# boardv3.net
KiCad netlist of a schematic drawn in EAGLE
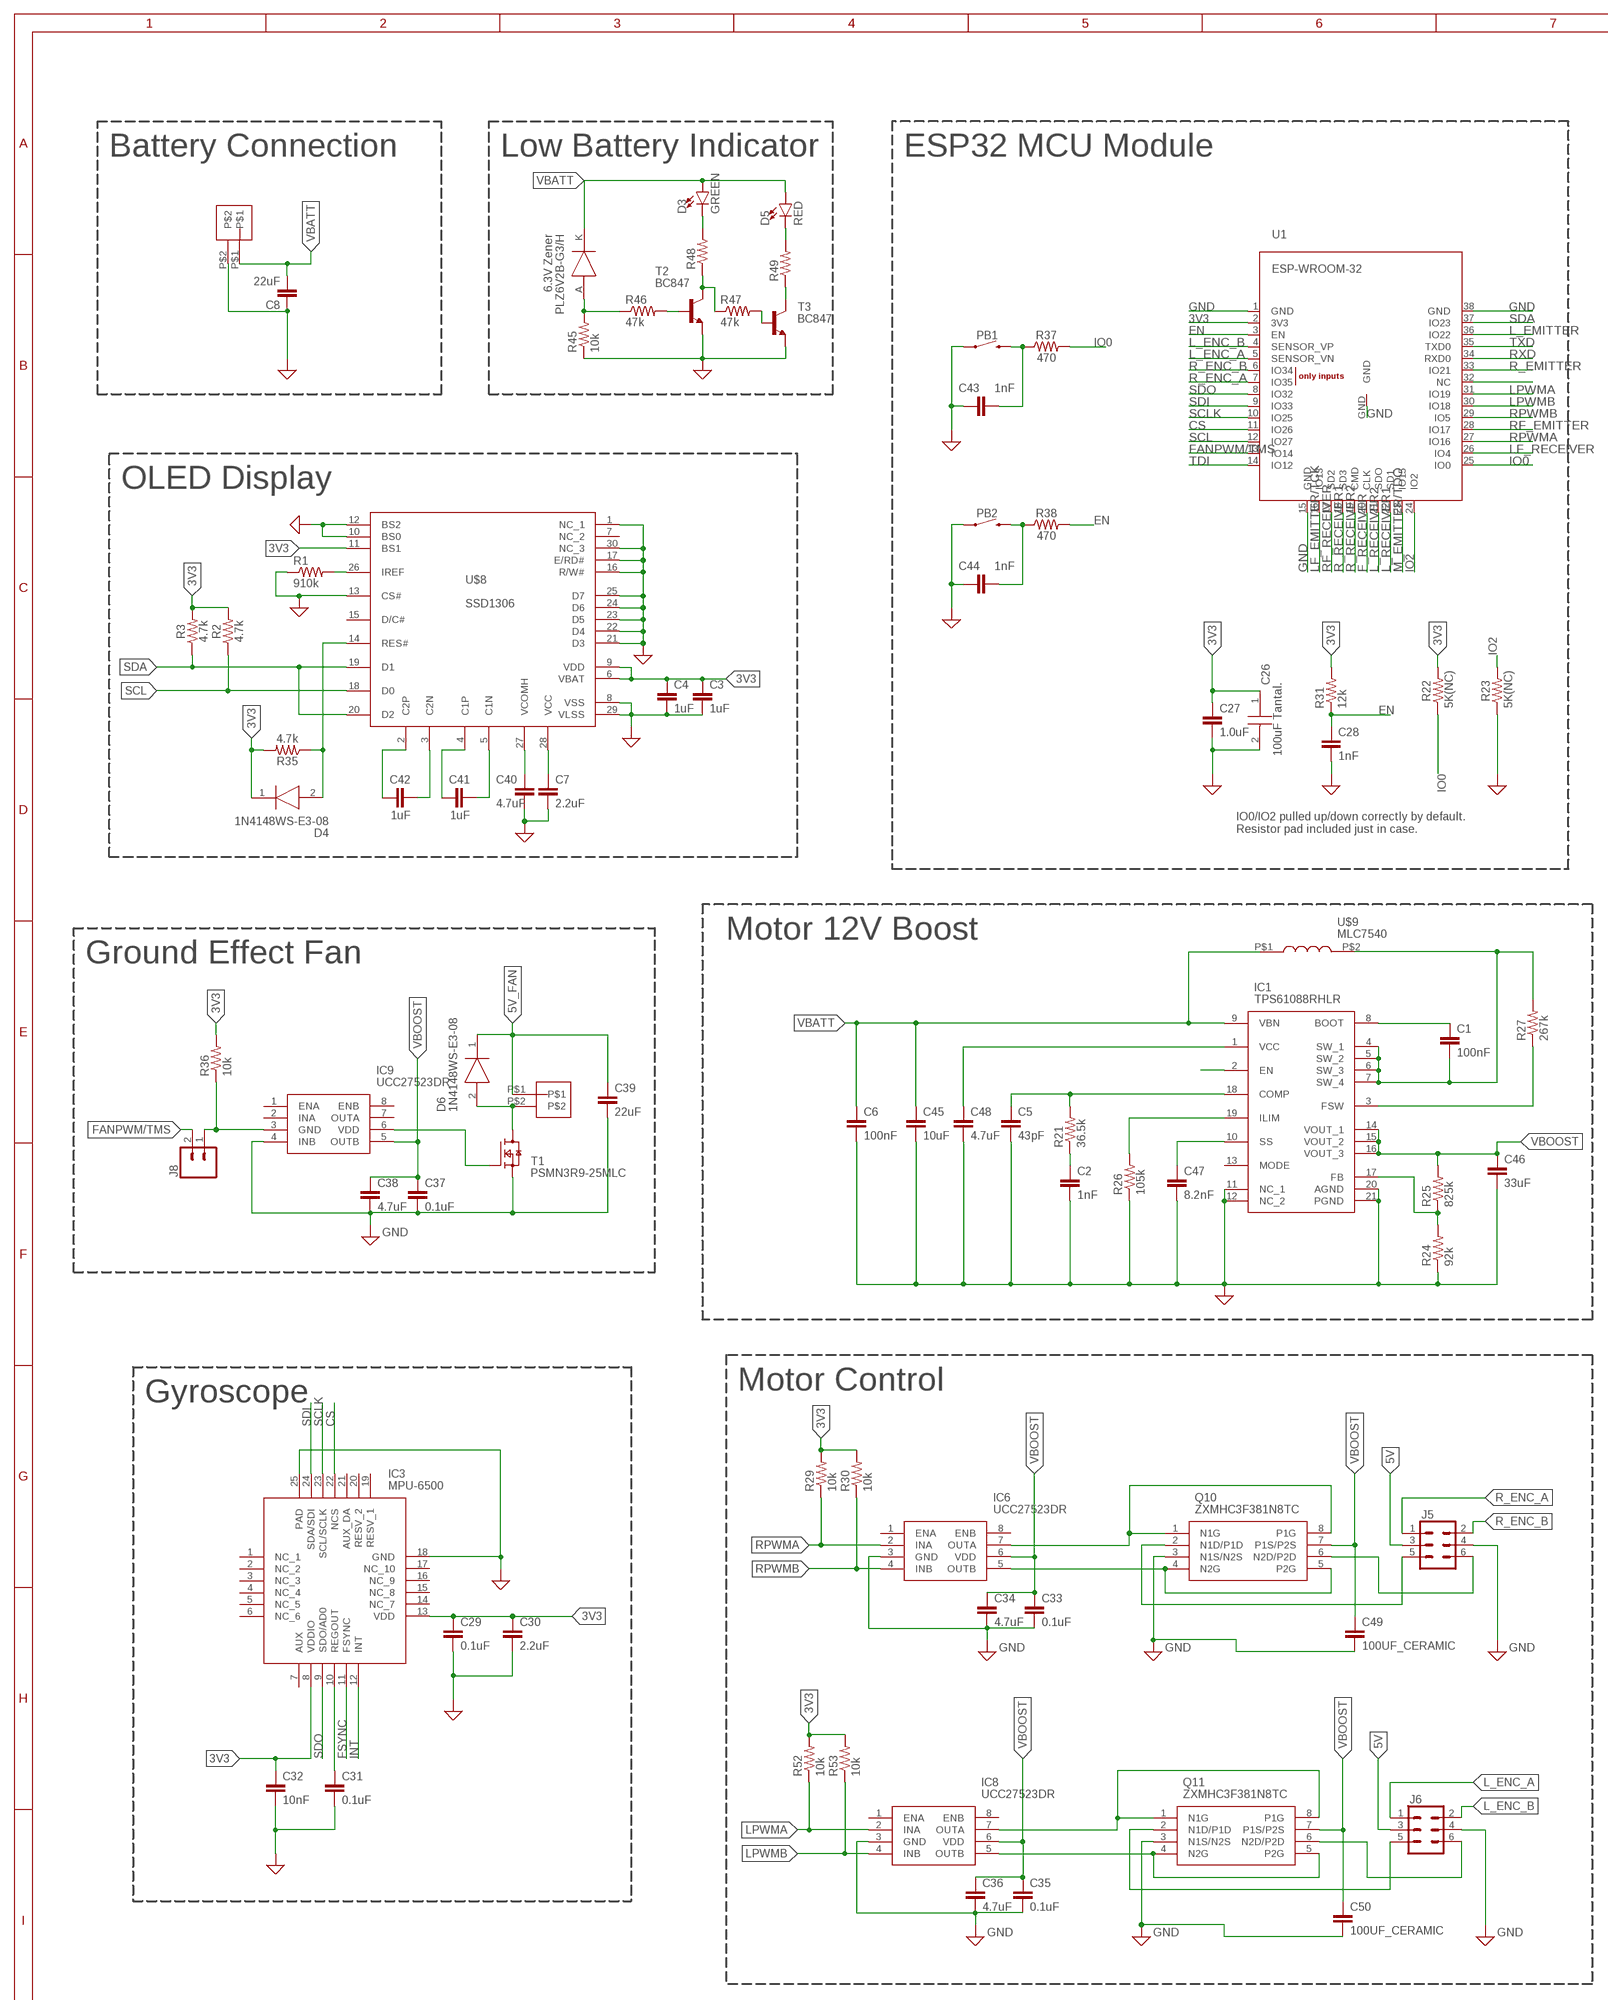
[diagram p0: schematic, sheet 1, part 1 of 2]
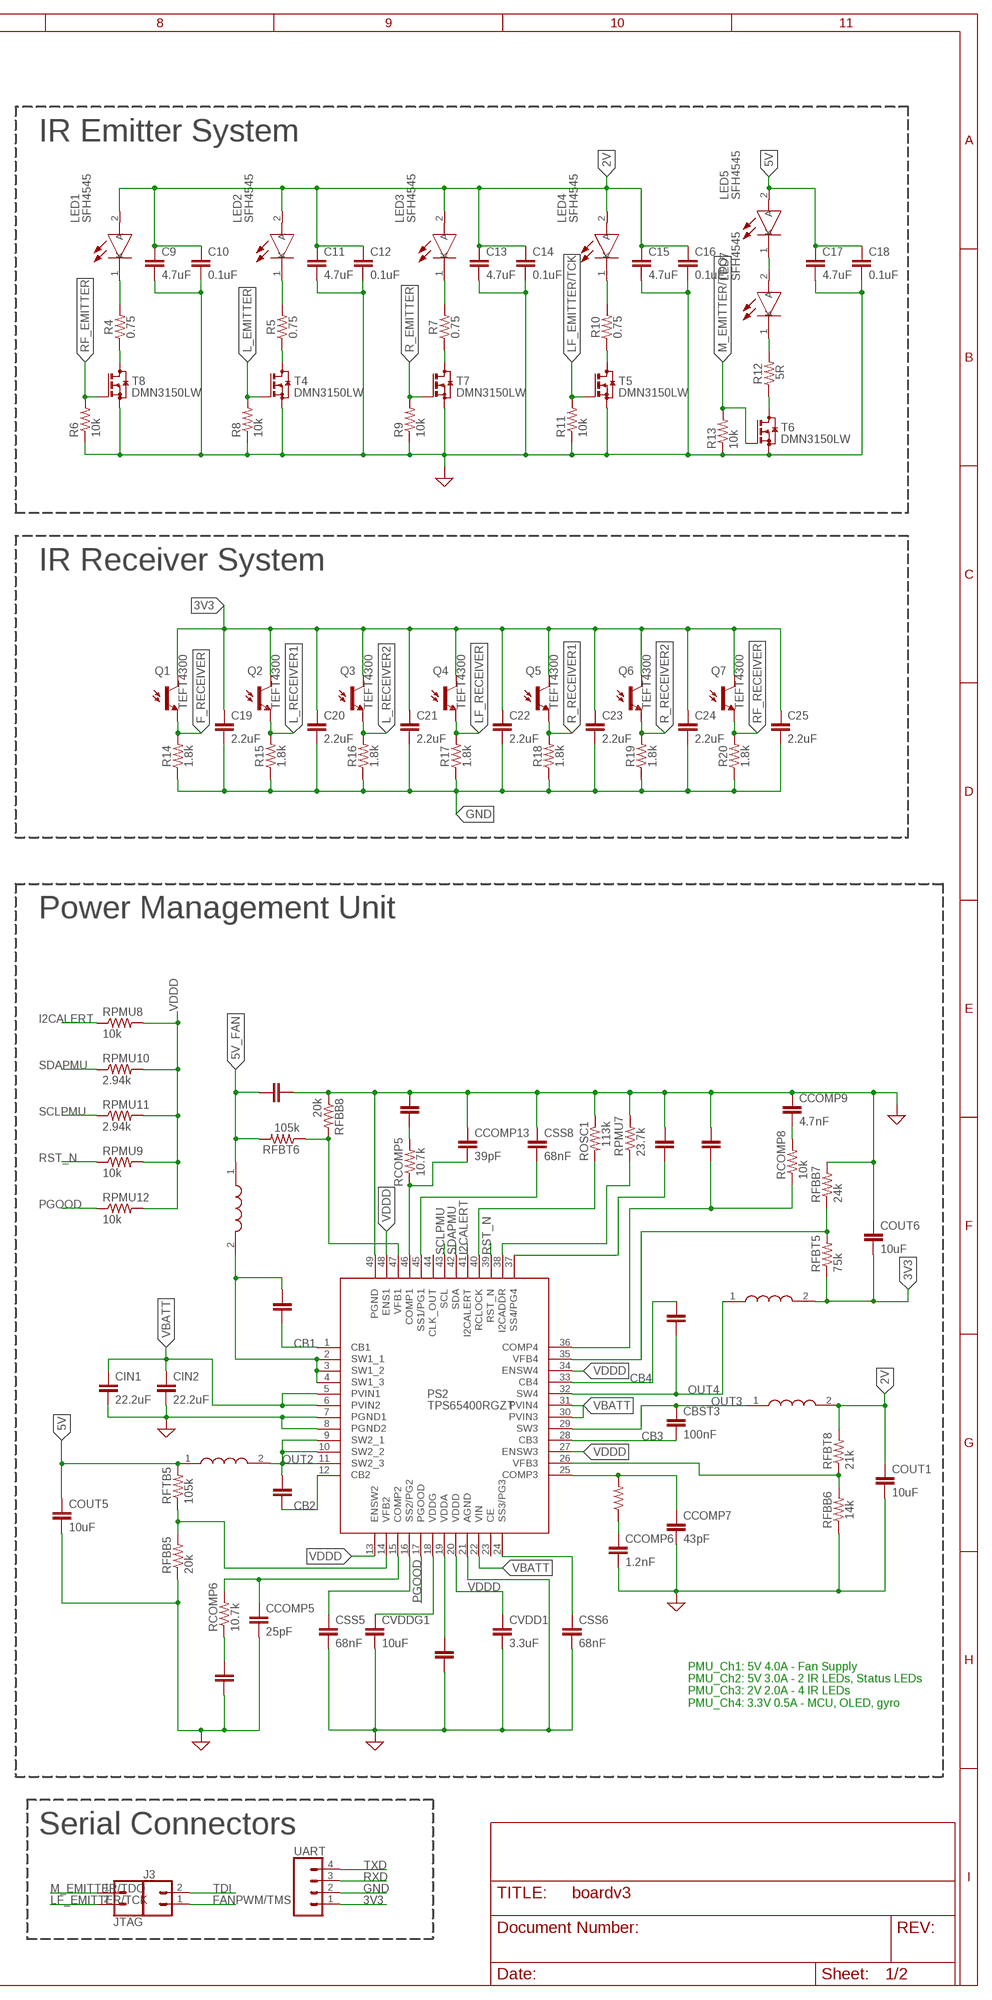
[diagram p1: schematic, sheet 1, part 2 of 2]
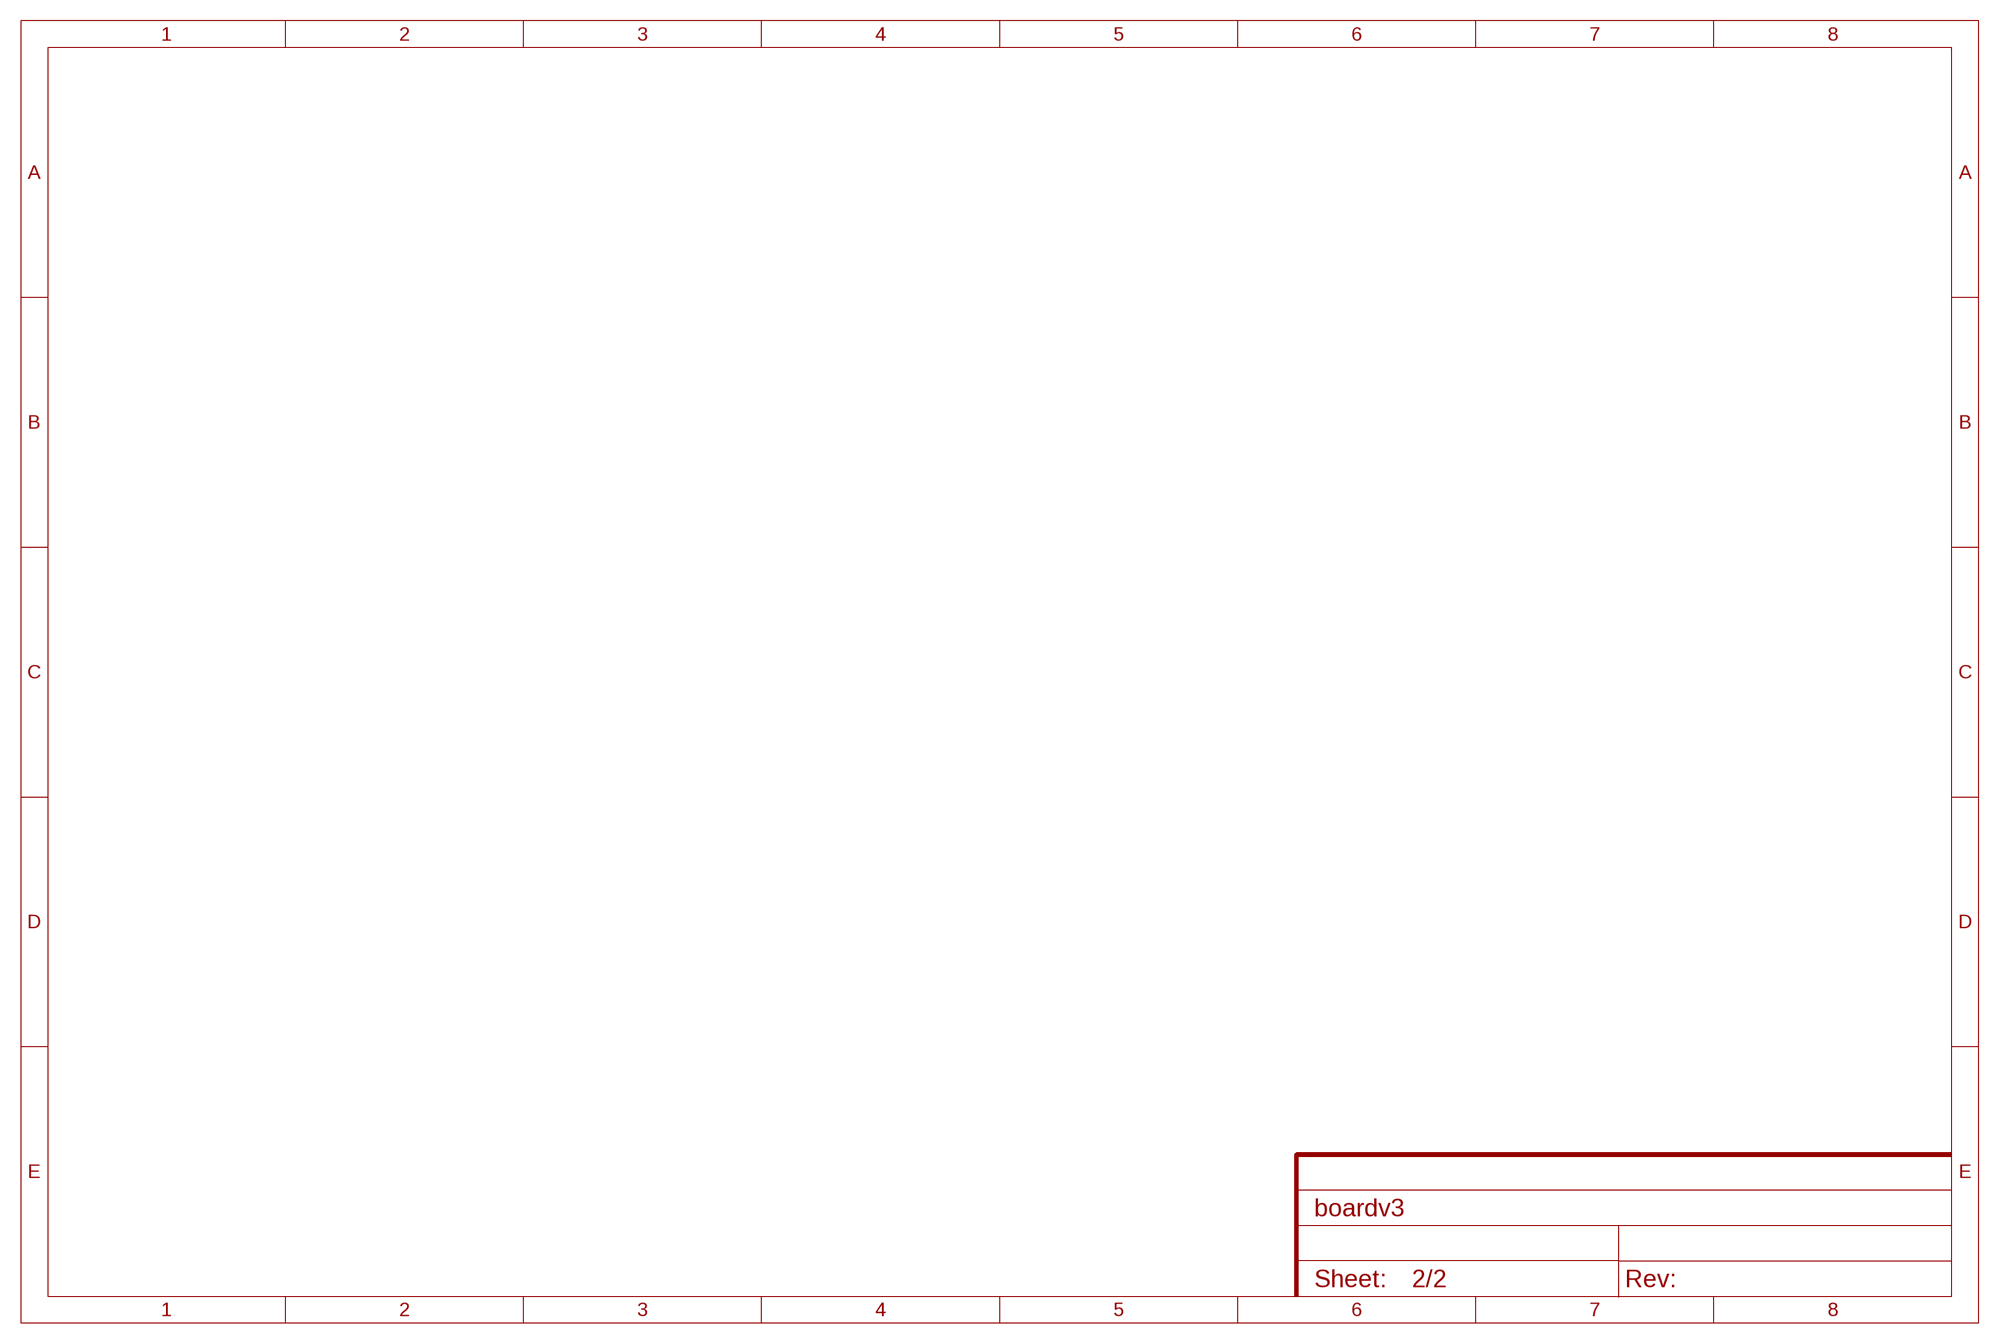
[diagram p2: schematic, sheet 2]

(export (version "E")
  (design (tool "Eeschema 10.0.6"))
  (components
    (comp (ref "C1")
      (value "100nF")
      (footprint "eagle-import:C0402")
      (libsource (lib "eagle-import") (part "C-EUC0402"))
    )
    (comp (ref "C2")
      (value "1nF")
      (footprint "eagle-import:C0805")
      (libsource (lib "eagle-import") (part "C-EUC0805"))
    )
    (comp (ref "C3")
      (value "1uF")
      (footprint "eagle-import:C0402")
      (libsource (lib "eagle-import") (part "resistor_348_C-EUC0402"))
    )
    (comp (ref "C4")
      (value "1uF")
      (footprint "eagle-import:C0402")
      (libsource (lib "eagle-import") (part "resistor_348_C-EUC0402"))
    )
    (comp (ref "C5")
      (value "43pF")
      (footprint "eagle-import:C0402")
      (libsource (lib "eagle-import") (part "C-EUC0402"))
    )
    (comp (ref "C6")
      (value "100nF")
      (footprint "eagle-import:C0805")
      (libsource (lib "eagle-import") (part "C-EUC0805"))
    )
    (comp (ref "C7")
      (value "2.2uF")
      (footprint "eagle-import:C0402")
      (libsource (lib "eagle-import") (part "resistor_348_C-EUC0402"))
    )
    (comp (ref "C8")
      (value "22uF")
      (footprint "eagle-import:0805")
      (libsource (lib "eagle-import") (part "22UF-0805-6.3V-20%"))
    )
    (comp (ref "C9")
      (value "4.7uF")
      (footprint "eagle-import:0603")
      (libsource (lib "eagle-import") (part "4.7UF0603"))
    )
    (comp (ref "C10")
      (value "0.1uF")
      (footprint "eagle-import:C0402")
      (libsource (lib "eagle-import") (part "C-EUC0402"))
    )
    (comp (ref "C11")
      (value "4.7uF")
      (footprint "eagle-import:0603")
      (libsource (lib "eagle-import") (part "4.7UF0603"))
    )
    (comp (ref "C12")
      (value "0.1uF")
      (footprint "eagle-import:C0402")
      (libsource (lib "eagle-import") (part "C-EUC0402"))
    )
    (comp (ref "C13")
      (value "4.7uF")
      (footprint "eagle-import:0603")
      (libsource (lib "eagle-import") (part "4.7UF0603"))
    )
    (comp (ref "C14")
      (value "0.1uF")
      (footprint "eagle-import:C0402")
      (libsource (lib "eagle-import") (part "C-EUC0402"))
    )
    (comp (ref "C15")
      (value "4.7uF")
      (footprint "eagle-import:0603")
      (libsource (lib "eagle-import") (part "4.7UF0603"))
    )
    (comp (ref "C16")
      (value "0.1uF")
      (footprint "eagle-import:C0402")
      (libsource (lib "eagle-import") (part "C-EUC0402"))
    )
    (comp (ref "C17")
      (value "4.7uF")
      (footprint "eagle-import:0603")
      (libsource (lib "eagle-import") (part "4.7UF0603"))
    )
    (comp (ref "C18")
      (value "0.1uF")
      (footprint "eagle-import:C0402")
      (libsource (lib "eagle-import") (part "C-EUC0402"))
    )
    (comp (ref "C19")
      (value "2.2uF")
      (footprint "eagle-import:0603")
      (libsource (lib "eagle-import") (part "2.2UF-0603-10V-20%"))
    )
    (comp (ref "C20")
      (value "2.2uF")
      (footprint "eagle-import:0603")
      (libsource (lib "eagle-import") (part "2.2UF-0603-10V-20%"))
    )
    (comp (ref "C21")
      (value "2.2uF")
      (footprint "eagle-import:0603")
      (libsource (lib "eagle-import") (part "2.2UF-0603-10V-20%"))
    )
    (comp (ref "C22")
      (value "2.2uF")
      (footprint "eagle-import:0603")
      (libsource (lib "eagle-import") (part "2.2UF-0603-10V-20%"))
    )
    (comp (ref "C23")
      (value "2.2uF")
      (footprint "eagle-import:0603")
      (libsource (lib "eagle-import") (part "2.2UF-0603-10V-20%"))
    )
    (comp (ref "C24")
      (value "2.2uF")
      (footprint "eagle-import:0603")
      (libsource (lib "eagle-import") (part "2.2UF-0603-10V-20%"))
    )
    (comp (ref "C25")
      (value "2.2uF")
      (footprint "eagle-import:0603")
      (libsource (lib "eagle-import") (part "2.2UF-0603-10V-20%"))
    )
    (comp (ref "C26")
      (value "100uF Tantal.")
      (footprint "eagle-import:CAPPM3528X210N")
      (fields (field (name "ARROW_PART_NUMBER") "TPSB107K006R0400") (field (name "RS_PART_NUMBER") "1243324"))
      (libsource (lib "eagle-import") (part "TPSB107K006R0400"))
    )
    (comp (ref "C27")
      (value "1.0uF")
      (footprint "eagle-import:0402")
      (libsource (lib "eagle-import") (part "1.0UF-0402-16V-10%"))
    )
    (comp (ref "C28")
      (value "1nF")
      (footprint "eagle-import:0603")
      (libsource (lib "eagle-import") (part "1.0NF/1000PF-0603-50V-10%"))
    )
    (comp (ref "C29")
      (value "0.1uF")
      (footprint "eagle-import:0603")
      (libsource (lib "eagle-import") (part "0.1UF-0603-25V-(+80/-20%)"))
    )
    (comp (ref "C30")
      (value "2.2uF")
      (footprint "eagle-import:0603")
      (libsource (lib "eagle-import") (part "2.2UF-0603-10V-20%"))
    )
    (comp (ref "C31")
      (value "0.1uF")
      (footprint "eagle-import:0603")
      (libsource (lib "eagle-import") (part "0.1UF-0603-25V-(+80/-20%)"))
    )
    (comp (ref "C32")
      (value "10nF")
      (footprint "eagle-import:0603")
      (libsource (lib "eagle-import") (part "10NF-0603-50V-10%"))
    )
    (comp (ref "C33")
      (value "0.1uF")
      (footprint "eagle-import:0603")
      (libsource (lib "eagle-import") (part "0.1UF-0603-25V-(+80/-20%)"))
    )
    (comp (ref "C34")
      (value "4.7uF")
      (footprint "eagle-import:0603")
      (libsource (lib "eagle-import") (part "4.7UF0603"))
    )
    (comp (ref "C35")
      (value "0.1uF")
      (footprint "eagle-import:0603")
      (libsource (lib "eagle-import") (part "0.1UF-0603-25V-(+80/-20%)"))
    )
    (comp (ref "C36")
      (value "4.7uF")
      (footprint "eagle-import:0603")
      (libsource (lib "eagle-import") (part "4.7UF0603"))
    )
    (comp (ref "C37")
      (value "0.1uF")
      (footprint "eagle-import:0603")
      (libsource (lib "eagle-import") (part "0.1UF-0603-25V-(+80/-20%)"))
    )
    (comp (ref "C38")
      (value "4.7uF")
      (footprint "eagle-import:0603")
      (libsource (lib "eagle-import") (part "4.7UF0603"))
    )
    (comp (ref "C39")
      (value "22uF")
      (footprint "eagle-import:0805")
      (libsource (lib "eagle-import") (part "22UF-0805-6.3V-20%"))
    )
    (comp (ref "C40")
      (value "4.7uF")
      (footprint "eagle-import:C0402")
      (libsource (lib "eagle-import") (part "resistor_348_C-EUC0402"))
    )
    (comp (ref "C41")
      (value "1uF")
      (footprint "eagle-import:C0402")
      (libsource (lib "eagle-import") (part "resistor_348_C-EUC0402"))
    )
    (comp (ref "C42")
      (value "1uF")
      (footprint "eagle-import:C0402")
      (libsource (lib "eagle-import") (part "resistor_348_C-EUC0402"))
    )
    (comp (ref "C43")
      (value "1nF")
      (footprint "eagle-import:0603")
      (libsource (lib "eagle-import") (part "1.0NF/1000PF-0603-50V-10%"))
    )
    (comp (ref "C44")
      (value "1nF")
      (footprint "eagle-import:0603")
      (libsource (lib "eagle-import") (part "1.0NF/1000PF-0603-50V-10%"))
    )
    (comp (ref "C45")
      (value "10uF")
      (footprint "eagle-import:C0402")
      (libsource (lib "eagle-import") (part "C-EUC0402"))
    )
    (comp (ref "C46")
      (value "33uF")
      (footprint "eagle-import:C1206")
      (libsource (lib "eagle-import") (part "C-EUC1206"))
    )
    (comp (ref "C47")
      (value "8.2nF")
      (footprint "eagle-import:C0805")
      (libsource (lib "eagle-import") (part "C-EUC0805"))
    )
    (comp (ref "C48")
      (value "4.7uF")
      (footprint "eagle-import:C0402")
      (libsource (lib "eagle-import") (part "C-EUC0402"))
    )
    (comp (ref "C49")
      (value "100UF_CERAMIC")
      (footprint "eagle-import:C1210")
      (libsource (lib "eagle-import") (part "100UF_CERAMIC"))
    )
    (comp (ref "C50")
      (value "100UF_CERAMIC")
      (footprint "eagle-import:C1210")
      (libsource (lib "eagle-import") (part "100UF_CERAMIC"))
    )
    (comp (ref "CBST1")
      (value "100nF")
      (footprint "eagle-import:C0402")
      (libsource (lib "eagle-import") (part "resistor_348_C-EUC0402"))
    )
    (comp (ref "CBST2")
      (value "100nF")
      (footprint "eagle-import:C0402")
      (libsource (lib "eagle-import") (part "resistor_348_C-EUC0402"))
    )
    (comp (ref "CBST3")
      (value "100nF")
      (footprint "eagle-import:C0402")
      (libsource (lib "eagle-import") (part "resistor_348_C-EUC0402"))
    )
    (comp (ref "CBST4")
      (value "100nF")
      (footprint "eagle-import:C0402")
      (libsource (lib "eagle-import") (part "resistor_348_C-EUC0402"))
    )
    (comp (ref "CCOMP5")
      (value "25pF")
      (footprint "eagle-import:C0603")
      (libsource (lib "eagle-import") (part "C-EUC0603"))
    )
    (comp (ref "CCOMP6")
      (value "1.2nF")
      (footprint "eagle-import:C0603")
      (libsource (lib "eagle-import") (part "C-EUC0603"))
    )
    (comp (ref "CCOMP7")
      (value "43pF")
      (footprint "eagle-import:C0603")
      (libsource (lib "eagle-import") (part "resistor_348_C-EUC0603"))
    )
    (comp (ref "CCOMP8")
      (value "1.8nF")
      (footprint "eagle-import:C0603")
      (libsource (lib "eagle-import") (part "resistor_348_C-EUC0603"))
    )
    (comp (ref "CCOMP9")
      (value "4.7nF")
      (footprint "eagle-import:C0603")
      (libsource (lib "eagle-import") (part "C-EUC0603"))
    )
    (comp (ref "CCOMP10")
      (value "82pF")
      (footprint "eagle-import:C0603")
      (libsource (lib "eagle-import") (part "C-EUC0603"))
    )
    (comp (ref "CCOMP11")
      (value "1.2nF")
      (footprint "eagle-import:C0603")
      (libsource (lib "eagle-import") (part "resistor_348_C-EUC0603"))
    )
    (comp (ref "CCOMP13")
      (value "39pF")
      (footprint "eagle-import:C0603")
      (libsource (lib "eagle-import") (part "resistor_348_C-EUC0603"))
    )
    (comp (ref "CIN1")
      (value "22.2uF")
      (footprint "eagle-import:0805")
      (libsource (lib "eagle-import") (part "10UF-0805-10V-10%"))
    )
    (comp (ref "CIN2")
      (value "22.2uF")
      (footprint "eagle-import:0805")
      (libsource (lib "eagle-import") (part "10UF-0805-10V-10%"))
    )
    (comp (ref "CIN3")
      (value "22.2uF")
      (footprint "eagle-import:0805")
      (libsource (lib "eagle-import") (part "10UF-0805-10V-10%"))
    )
    (comp (ref "COUT1")
      (value "10uF")
      (footprint "eagle-import:C0402")
      (libsource (lib "eagle-import") (part "resistor_348_C-EUC0402"))
    )
    (comp (ref "COUT5")
      (value "10uF")
      (footprint "eagle-import:C0402")
      (libsource (lib "eagle-import") (part "resistor_348_C-EUC0402"))
    )
    (comp (ref "COUT6")
      (value "10uF")
      (footprint "eagle-import:C0402")
      (libsource (lib "eagle-import") (part "resistor_348_C-EUC0402"))
    )
    (comp (ref "CSS5")
      (value "68nF")
      (footprint "eagle-import:C0402")
      (libsource (lib "eagle-import") (part "resistor_348_C-EUC0402"))
    )
    (comp (ref "CSS6")
      (value "68nF")
      (footprint "eagle-import:C0402")
      (libsource (lib "eagle-import") (part "resistor_348_C-EUC0402"))
    )
    (comp (ref "CSS7")
      (value "68nF")
      (footprint "eagle-import:C0402")
      (libsource (lib "eagle-import") (part "resistor_348_C-EUC0402"))
    )
    (comp (ref "CSS8")
      (value "68nF")
      (footprint "eagle-import:C0402")
      (libsource (lib "eagle-import") (part "resistor_348_C-EUC0402"))
    )
    (comp (ref "CVDD1")
      (value "3.3uF")
      (footprint "eagle-import:C0402")
      (libsource (lib "eagle-import") (part "resistor_348_C-EUC0402"))
    )
    (comp (ref "CVDDA1")
      (value "4.7uF")
      (footprint "eagle-import:0603")
      (libsource (lib "eagle-import") (part "4.7UF0603"))
    )
    (comp (ref "CVDDG1")
      (value "10uF")
      (footprint "eagle-import:C0603")
      (libsource (lib "eagle-import") (part "resistor_348_C-EUC0603"))
    )
    (comp (ref "D3")
      (value "GREEN")
      (footprint "eagle-import:LED-0603")
      (libsource (lib "eagle-import") (part "LED-GREEN0603"))
    )
    (comp (ref "D4")
      (value "1N4148WS-E3-08")
      (footprint "eagle-import:SOD2713X115N")
      (fields (field (name "RS_PART_NUMBER") "7003677P"))
      (libsource (lib "eagle-import") (part "1N4148WS-E3-08"))
    )
    (comp (ref "D5")
      (value "RED")
      (footprint "eagle-import:LED-0603")
      (libsource (lib "eagle-import") (part "LED-RED0603"))
    )
    (comp (ref "D6")
      (value "1N4148WS-E3-08")
      (footprint "eagle-import:SOD2713X115N")
      (fields (field (name "RS_PART_NUMBER") "7003677P"))
      (libsource (lib "eagle-import") (part "1N4148WS-E3-08"))
    )
    (comp (ref "IC1")
      (value "TPS61088RHLR")
      (footprint "eagle-import:RHL(R-PVQFN-N20)_1")
      (libsource (lib "eagle-import") (part "TPS61088RHLR"))
    )
    (comp (ref "IC3")
      (value "MPU-6500")
      (footprint "eagle-import:QFN40P300X300X95-25N")
      (libsource (lib "eagle-import") (part "MPU-6500"))
    )
    (comp (ref "IC6")
      (value "UCC27523DR")
      (footprint "eagle-import:SOIC127P600X175-8N")
      (libsource (lib "eagle-import") (part "UCC27523DR"))
    )
    (comp (ref "IC8")
      (value "UCC27523DR")
      (footprint "eagle-import:SOIC127P600X175-8N")
      (libsource (lib "eagle-import") (part "UCC27523DR"))
    )
    (comp (ref "IC9")
      (value "UCC27523DR")
      (footprint "eagle-import:SOIC127P600X175-8N")
      (libsource (lib "eagle-import") (part "UCC27523DR"))
    )
    (comp (ref "J2")
      (value "2_PIN_JST-XH")
      (footprint "eagle-import:2_PIN_JST-XH")
      (libsource (lib "eagle-import") (part "2_PIN_JST-XH"))
    )
    (comp (ref "J3")
      (value "CONN_02")
      (footprint "eagle-import:1X02")
      (libsource (lib "eagle-import") (part "CONN_02"))
    )
    (comp (ref "J5")
      (value "CONN_03X22X3_SILK_MALE_PTH")
      (footprint "eagle-import:2X3")
      (libsource (lib "eagle-import") (part "CONN_03X22X3_SILK_MALE_PTH"))
    )
    (comp (ref "J6")
      (value "CONN_03X22X3_SILK_MALE_PTH")
      (footprint "eagle-import:2X3")
      (libsource (lib "eagle-import") (part "CONN_03X22X3_SILK_MALE_PTH"))
    )
    (comp (ref "J7")
      (value "2_PIN_JST-XH")
      (footprint "eagle-import:2_PIN_JST-XH")
      (libsource (lib "eagle-import") (part "2_PIN_JST-XH"))
    )
    (comp (ref "J8")
      (value "CONN_02")
      (footprint "eagle-import:1X02")
      (libsource (lib "eagle-import") (part "CONN_02"))
    )
    (comp (ref "JTAG")
      (value "CONN_02")
      (footprint "eagle-import:1X02")
      (libsource (lib "eagle-import") (part "CONN_02"))
    )
    (comp (ref "L5")
      (value "XAL4030-332MEB")
      (footprint "eagle-import:XAL4030-332MEB")
      (libsource (lib "eagle-import") (part "XAL4030-332MEB"))
    )
    (comp (ref "L6")
      (value "SDR0302-100ML")
      (footprint "eagle-import:SDR0302-471KL")
      (fields (field (name "ARROW_PART_NUMBER") "SDR0302-1R2ML"))
      (libsource (lib "eagle-import") (part "SDR0302-1R2ML"))
    )
    (comp (ref "L7")
      (value "XAL4030-472MEB")
      (footprint "eagle-import:XAL4030-332MEB")
      (fields (field (name "ARROW_PART_NUMBER") "XAL4030-332MEB"))
      (libsource (lib "eagle-import") (part "XAL4030-332MEB"))
    )
    (comp (ref "L8")
      (value "XFL4020-472MEB")
      (footprint "eagle-import:XFL4020-222ME")
      (fields (field (name "ARROW_PART_NUMBER") "XFL4020-332MEB"))
      (libsource (lib "eagle-import") (part "XFL4020-332MEB"))
    )
    (comp (ref "LED1")
      (value "SFH4545")
      (footprint "eagle-import:SFH_4556P")
      (fields (field (name "ARROW_PART_NUMBER") "SFH4550"))
      (libsource (lib "eagle-import") (part "SFH4550"))
    )
    (comp (ref "LED2")
      (value "SFH4545")
      (footprint "eagle-import:SFH_4556P")
      (fields (field (name "ARROW_PART_NUMBER") "SFH4550"))
      (libsource (lib "eagle-import") (part "SFH4550"))
    )
    (comp (ref "LED3")
      (value "SFH4545")
      (footprint "eagle-import:SFH_4556P")
      (fields (field (name "ARROW_PART_NUMBER") "SFH4550"))
      (libsource (lib "eagle-import") (part "SFH4550"))
    )
    (comp (ref "LED4")
      (value "SFH4545")
      (footprint "eagle-import:SFH_4556P")
      (fields (field (name "ARROW_PART_NUMBER") "SFH4550"))
      (libsource (lib "eagle-import") (part "SFH4550"))
    )
    (comp (ref "LED5")
      (value "SFH4545")
      (footprint "eagle-import:SFH_4556P")
      (fields (field (name "ARROW_PART_NUMBER") "SFH4550"))
      (libsource (lib "eagle-import") (part "SFH4550"))
    )
    (comp (ref "LED7")
      (value "SFH4545")
      (footprint "eagle-import:SFH_4556P")
      (fields (field (name "ARROW_PART_NUMBER") "SFH4550"))
      (libsource (lib "eagle-import") (part "SFH4550"))
    )
    (comp (ref "PB1")
      (value "SPST_3X6X2.5MMPB")
      (footprint "eagle-import:3X6X2.5MMSPB")
      (libsource (lib "eagle-import") (part "SPST_3X6X2.5MMPB"))
    )
    (comp (ref "PB2")
      (value "SPST_3X6X2.5MMPB")
      (footprint "eagle-import:3X6X2.5MMSPB")
      (libsource (lib "eagle-import") (part "SPST_3X6X2.5MMPB"))
    )
    (comp (ref "PLZ6V2B-G3/H")
      (value "6.3V Zener")
      (footprint "eagle-import:DO-219AC")
      (libsource (lib "eagle-import") (part "PLZ6V8C-HG3/H"))
    )
    (comp (ref "PS2")
      (value "TPS65400RGZT")
      (footprint "eagle-import:QFN50P700X700X100-49N")
      (fields (field (name "RS_PART_NUMBER") "1629904"))
      (libsource (lib "eagle-import") (part "TPS65400RGZT"))
    )
    (comp (ref "Q1")
      (value "TEFT4300")
      (footprint "eagle-import:TEFT4300")
      (fields (field (name "RS_PART_NUMBER") "7082731P"))
      (libsource (lib "eagle-import") (part "TEFT4300"))
    )
    (comp (ref "Q2")
      (value "TEFT4300")
      (footprint "eagle-import:TEFT4300")
      (fields (field (name "RS_PART_NUMBER") "7082731P"))
      (libsource (lib "eagle-import") (part "TEFT4300"))
    )
    (comp (ref "Q3")
      (value "TEFT4300")
      (footprint "eagle-import:TEFT4300")
      (fields (field (name "RS_PART_NUMBER") "7082731P"))
      (libsource (lib "eagle-import") (part "TEFT4300"))
    )
    (comp (ref "Q4")
      (value "TEFT4300")
      (footprint "eagle-import:TEFT4300")
      (fields (field (name "RS_PART_NUMBER") "7082731P"))
      (libsource (lib "eagle-import") (part "TEFT4300"))
    )
    (comp (ref "Q5")
      (value "TEFT4300")
      (footprint "eagle-import:TEFT4300")
      (fields (field (name "RS_PART_NUMBER") "7082731P"))
      (libsource (lib "eagle-import") (part "TEFT4300"))
    )
    (comp (ref "Q6")
      (value "TEFT4300")
      (footprint "eagle-import:TEFT4300")
      (fields (field (name "RS_PART_NUMBER") "7082731P"))
      (libsource (lib "eagle-import") (part "TEFT4300"))
    )
    (comp (ref "Q7")
      (value "TEFT4300")
      (footprint "eagle-import:TEFT4300")
      (fields (field (name "RS_PART_NUMBER") "7082731P"))
      (libsource (lib "eagle-import") (part "TEFT4300"))
    )
    (comp (ref "Q10")
      (value "ZXMHC3F381N8TC")
      (footprint "eagle-import:SOIC127P600X175-8N")
      (fields (field (name "RS_PART_NUMBER") "7515344P"))
      (libsource (lib "eagle-import") (part "ZXMHC3F381N8TC"))
    )
    (comp (ref "Q11")
      (value "ZXMHC3F381N8TC")
      (footprint "eagle-import:SOIC127P600X175-8N")
      (fields (field (name "RS_PART_NUMBER") "7515344P"))
      (libsource (lib "eagle-import") (part "ZXMHC3F381N8TC"))
    )
    (comp (ref "R1")
      (value "910k")
      (footprint "eagle-import:R0402")
      (libsource (lib "eagle-import") (part "R-US_R0402"))
    )
    (comp (ref "R2")
      (value "4.7k")
      (footprint "eagle-import:0603")
      (libsource (lib "eagle-import") (part "4.7KOHM-0603-1/10W-1%"))
    )
    (comp (ref "R3")
      (value "4.7k")
      (footprint "eagle-import:0603")
      (libsource (lib "eagle-import") (part "4.7KOHM-0603-1/10W-1%"))
    )
    (comp (ref "R4")
      (value "0.75")
      (footprint "eagle-import:0805")
      (libsource (lib "eagle-import") (part "0.75OHM-0805-1/4W-1%"))
    )
    (comp (ref "R5")
      (value "0.75")
      (footprint "eagle-import:0805")
      (libsource (lib "eagle-import") (part "0.75OHM-0805-1/4W-1%"))
    )
    (comp (ref "R6")
      (value "10k")
      (footprint "eagle-import:R0201")
      (libsource (lib "eagle-import") (part "R-US_R0201"))
    )
    (comp (ref "R7")
      (value "0.75")
      (footprint "eagle-import:0805")
      (libsource (lib "eagle-import") (part "0.75OHM-0805-1/4W-1%"))
    )
    (comp (ref "R8")
      (value "10k")
      (footprint "eagle-import:R0201")
      (libsource (lib "eagle-import") (part "R-US_R0201"))
    )
    (comp (ref "R9")
      (value "10k")
      (footprint "eagle-import:R0201")
      (libsource (lib "eagle-import") (part "R-US_R0201"))
    )
    (comp (ref "R10")
      (value "0.75")
      (footprint "eagle-import:0805")
      (libsource (lib "eagle-import") (part "0.75OHM-0805-1/4W-1%"))
    )
    (comp (ref "R11")
      (value "10k")
      (footprint "eagle-import:R0201")
      (libsource (lib "eagle-import") (part "R-US_R0201"))
    )
    (comp (ref "R12")
      (value "5R")
      (footprint "eagle-import:0805")
      (libsource (lib "eagle-import") (part "RESISTOR0805"))
    )
    (comp (ref "R13")
      (value "10k")
      (footprint "eagle-import:R0201")
      (libsource (lib "eagle-import") (part "R-US_R0201"))
    )
    (comp (ref "R14")
      (value "1.8k")
      (footprint "eagle-import:0603")
      (libsource (lib "eagle-import") (part "1.8KOHM-0603-1/10W-1%"))
    )
    (comp (ref "R15")
      (value "1.8k")
      (footprint "eagle-import:0603")
      (libsource (lib "eagle-import") (part "1.8KOHM-0603-1/10W-1%"))
    )
    (comp (ref "R16")
      (value "1.8k")
      (footprint "eagle-import:0603")
      (libsource (lib "eagle-import") (part "1.8KOHM-0603-1/10W-1%"))
    )
    (comp (ref "R17")
      (value "1.8k")
      (footprint "eagle-import:0603")
      (libsource (lib "eagle-import") (part "1.8KOHM-0603-1/10W-1%"))
    )
    (comp (ref "R18")
      (value "1.8k")
      (footprint "eagle-import:0603")
      (libsource (lib "eagle-import") (part "1.8KOHM-0603-1/10W-1%"))
    )
    (comp (ref "R19")
      (value "1.8k")
      (footprint "eagle-import:0603")
      (libsource (lib "eagle-import") (part "1.8KOHM-0603-1/10W-1%"))
    )
    (comp (ref "R20")
      (value "1.8k")
      (footprint "eagle-import:0603")
      (libsource (lib "eagle-import") (part "1.8KOHM-0603-1/10W-1%"))
    )
    (comp (ref "R21")
      (value "36.5k")
      (footprint "eagle-import:R0201")
      (libsource (lib "eagle-import") (part "R-US_R0201"))
    )
    (comp (ref "R22")
      (value "5K(NC)")
      (footprint "eagle-import:0402")
      (libsource (lib "eagle-import") (part "RESISTOR0402"))
    )
    (comp (ref "R23")
      (value "5K(NC)")
      (footprint "eagle-import:0402")
      (libsource (lib "eagle-import") (part "RESISTOR0402"))
    )
    (comp (ref "R24")
      (value "92k")
      (footprint "eagle-import:R0805")
      (libsource (lib "eagle-import") (part "R-US_R0805"))
    )
    (comp (ref "R25")
      (value "825k")
      (footprint "eagle-import:R0402")
      (libsource (lib "eagle-import") (part "R-US_R0402"))
    )
    (comp (ref "R26")
      (value "105k")
      (footprint "eagle-import:R0201")
      (libsource (lib "eagle-import") (part "R-US_R0201"))
    )
    (comp (ref "R27")
      (value "267k")
      (footprint "eagle-import:R0402")
      (libsource (lib "eagle-import") (part "R-US_R0402"))
    )
    (comp (ref "R29")
      (value "10k")
      (footprint "eagle-import:R0201")
      (libsource (lib "eagle-import") (part "R-US_R0201"))
    )
    (comp (ref "R30")
      (value "10k")
      (footprint "eagle-import:R0201")
      (libsource (lib "eagle-import") (part "R-US_R0201"))
    )
    (comp (ref "R31")
      (value "12k")
      (footprint "eagle-import:R0201")
      (libsource (lib "eagle-import") (part "R-US_R0201"))
    )
    (comp (ref "R35")
      (value "4.7k")
      (footprint "eagle-import:0603")
      (libsource (lib "eagle-import") (part "4.7KOHM-0603-1/10W-1%"))
    )
    (comp (ref "R36")
      (value "10k")
      (footprint "eagle-import:R0201")
      (libsource (lib "eagle-import") (part "R-US_R0201"))
    )
    (comp (ref "R37")
      (value "470")
      (footprint "eagle-import:0603")
      (libsource (lib "eagle-import") (part "470OHM-0603-1/10W-1%"))
    )
    (comp (ref "R38")
      (value "470")
      (footprint "eagle-import:0603")
      (libsource (lib "eagle-import") (part "470OHM-0603-1/10W-1%"))
    )
    (comp (ref "R45")
      (value "10k")
      (footprint "eagle-import:R0402")
      (libsource (lib "eagle-import") (part "R-US_R0402"))
    )
    (comp (ref "R46")
      (value "47k")
      (footprint "eagle-import:R0402")
      (libsource (lib "eagle-import") (part "R-US_R0402"))
    )
    (comp (ref "R47")
      (value "47k")
      (footprint "eagle-import:R0402")
      (libsource (lib "eagle-import") (part "R-US_R0402"))
    )
    (comp (ref "R48")
      (value "R-US_R0603")
      (footprint "eagle-import:R0603")
      (libsource (lib "eagle-import") (part "R-US_R0603"))
    )
    (comp (ref "R49")
      (value "R-US_R0603")
      (footprint "eagle-import:R0603")
      (libsource (lib "eagle-import") (part "R-US_R0603"))
    )
    (comp (ref "R52")
      (value "10k")
      (footprint "eagle-import:R0201")
      (libsource (lib "eagle-import") (part "R-US_R0201"))
    )
    (comp (ref "R53")
      (value "10k")
      (footprint "eagle-import:R0201")
      (libsource (lib "eagle-import") (part "R-US_R0201"))
    )
    (comp (ref "RCOMP5")
      (value "10.7k")
      (footprint "eagle-import:0402")
      (libsource (lib "eagle-import") (part "RESISTOR0402"))
    )
    (comp (ref "RCOMP6")
      (value "10.7k")
      (footprint "eagle-import:R0402")
      (libsource (lib "eagle-import") (part "R-US_R0402"))
    )
    (comp (ref "RCOMP7")
      (value "9.31k")
      (footprint "eagle-import:R0402")
      (libsource (lib "eagle-import") (part "R-US_R0402"))
    )
    (comp (ref "RCOMP8")
      (value "10k")
      (footprint "eagle-import:R0201")
      (libsource (lib "eagle-import") (part "resistor_348_R-US_R0201"))
    )
    (comp (ref "RFBB5")
      (value "20k")
      (footprint "eagle-import:R0805")
      (libsource (lib "eagle-import") (part "resistor_348_R-US_R0805"))
    )
    (comp (ref "RFBB6")
      (value "14k")
      (footprint "eagle-import:0402")
      (libsource (lib "eagle-import") (part "RESISTOR0402"))
    )
    (comp (ref "RFBB7")
      (value "24k")
      (footprint "eagle-import:R0805")
      (libsource (lib "eagle-import") (part "resistor_348_R-US_R0805"))
    )
    (comp (ref "RFBB8")
      (value "20k")
      (footprint "eagle-import:R0805")
      (libsource (lib "eagle-import") (part "R-US_R0805"))
    )
    (comp (ref "RFBT5")
      (value "75k")
      (footprint "eagle-import:R0402")
      (libsource (lib "eagle-import") (part "resistor_348_R-US_R0402"))
    )
    (comp (ref "RFBT6")
      (value "105k")
      (footprint "eagle-import:R0201")
      (libsource (lib "eagle-import") (part "R-US_R0201"))
    )
    (comp (ref "RFBT8")
      (value "21k")
      (footprint "eagle-import:R0402")
      (libsource (lib "eagle-import") (part "R-US_R0402"))
    )
    (comp (ref "RFTB5")
      (value "105k")
      (footprint "eagle-import:R0201")
      (libsource (lib "eagle-import") (part "R-US_R0201"))
    )
    (comp (ref "ROSC1")
      (value "113k")
      (footprint "eagle-import:R0402")
      (libsource (lib "eagle-import") (part "resistor_348_R-US_R0402"))
    )
    (comp (ref "RPMU7")
      (value "23.7k")
      (footprint "eagle-import:R0201")
      (libsource (lib "eagle-import") (part "resistor_348_R-US_R0201"))
    )
    (comp (ref "RPMU8")
      (value "10k")
      (footprint "eagle-import:R0201")
      (libsource (lib "eagle-import") (part "resistor_348_R-US_R0201"))
    )
    (comp (ref "RPMU9")
      (value "10k")
      (footprint "eagle-import:R0201")
      (libsource (lib "eagle-import") (part "resistor_348_R-US_R0201"))
    )
    (comp (ref "RPMU10")
      (value "2.94k")
      (footprint "eagle-import:R0402")
      (libsource (lib "eagle-import") (part "resistor_348_R-US_R0402"))
    )
    (comp (ref "RPMU11")
      (value "2.94k")
      (footprint "eagle-import:R0402")
      (libsource (lib "eagle-import") (part "resistor_348_R-US_R0402"))
    )
    (comp (ref "RPMU12")
      (value "10k")
      (footprint "eagle-import:R0201")
      (libsource (lib "eagle-import") (part "resistor_348_R-US_R0201"))
    )
    (comp (ref "T1")
      (value "PSMN3R9-25MLC")
      (footprint "eagle-import:SOT1210")
      (fields (field (name "VOLTAGE") "25V"))
      (libsource (lib "eagle-import") (part "PSMNMLC3R9-25"))
    )
    (comp (ref "T2")
      (value "BC847")
      (footprint "eagle-import:SOT23")
      (libsource (lib "eagle-import") (part "BC847"))
    )
    (comp (ref "T3")
      (value "BC847")
      (footprint "eagle-import:SOT23")
      (libsource (lib "eagle-import") (part "BC847"))
    )
    (comp (ref "T4")
      (value "DMN3150LW")
      (footprint "eagle-import:SOT323")
      (libsource (lib "eagle-import") (part "DMN3150LW"))
    )
    (comp (ref "T5")
      (value "DMN3150LW")
      (footprint "eagle-import:SOT323")
      (libsource (lib "eagle-import") (part "DMN3150LW"))
    )
    (comp (ref "T6")
      (value "DMN3150LW")
      (footprint "eagle-import:SOT323")
      (libsource (lib "eagle-import") (part "DMN3150LW"))
    )
    (comp (ref "T7")
      (value "DMN3150LW")
      (footprint "eagle-import:SOT323")
      (libsource (lib "eagle-import") (part "DMN3150LW"))
    )
    (comp (ref "T8")
      (value "DMN3150LW")
      (footprint "eagle-import:SOT323")
      (libsource (lib "eagle-import") (part "DMN3150LW"))
    )
    (comp (ref "U$8")
      (value "SSD1306")
      (footprint "eagle-import:30PINFPC_P0.7MM")
      (libsource (lib "eagle-import") (part "SSD1306"))
    )
    (comp (ref "U$9")
      (value "MLC7540")
      (footprint "eagle-import:MLC7540")
      (libsource (lib "eagle-import") (part "MLC7540"))
    )
    (comp (ref "U1")
      (value "ESP-WROOM-32")
      (footprint "eagle-import:ESP-WROOM-32")
      (libsource (lib "eagle-import") (part "ESP-WROOM-32"))
    )
    (comp (ref "UART")
      (value "CONN_04")
      (footprint "eagle-import:1X04")
      (libsource (lib "eagle-import") (part "CONN_04"))
    )
  )
  (nets
    (net (code "1") (name "2V") (class "Default")
      (node (ref "C10") (pin "1") (pinfunction "1_1") (pintype "passive"))
      (node (ref "C11") (pin "1") (pinfunction "1_1") (pintype "passive"))
      (node (ref "C12") (pin "1") (pinfunction "1_1") (pintype "passive"))
      (node (ref "C13") (pin "1") (pinfunction "1_1") (pintype "passive"))
      (node (ref "C14") (pin "1") (pinfunction "1_1") (pintype "passive"))
      (node (ref "C15") (pin "1") (pinfunction "1_1") (pintype "passive"))
      (node (ref "C16") (pin "1") (pinfunction "1_1") (pintype "passive"))
      (node (ref "C9") (pin "1") (pinfunction "1_1") (pintype "passive"))
      (node (ref "COUT1") (pin "1") (pinfunction "1_1") (pintype "passive"))
      (node (ref "L8") (pin "2") (pinfunction "2_2") (pintype "bidirectional"))
      (node (ref "LED1") (pin "2") (pinfunction "A_2") (pintype "bidirectional"))
      (node (ref "LED2") (pin "2") (pinfunction "A_2") (pintype "bidirectional"))
      (node (ref "LED3") (pin "2") (pinfunction "A_2") (pintype "bidirectional"))
      (node (ref "LED4") (pin "2") (pinfunction "A_2") (pintype "bidirectional"))
      (node (ref "RFBT8") (pin "2") (pinfunction "2_2") (pintype "passive"))
    )
    (net (code "2") (name "3V3") (class "Default")
      (node (ref "C19") (pin "1") (pinfunction "1_1") (pintype "passive"))
      (node (ref "C20") (pin "1") (pinfunction "1_1") (pintype "passive"))
      (node (ref "C21") (pin "1") (pinfunction "1_1") (pintype "passive"))
      (node (ref "C22") (pin "1") (pinfunction "1_1") (pintype "passive"))
      (node (ref "C23") (pin "1") (pinfunction "1_1") (pintype "passive"))
      (node (ref "C24") (pin "1") (pinfunction "1_1") (pintype "passive"))
      (node (ref "C25") (pin "1") (pinfunction "1_1") (pintype "passive"))
      (node (ref "C26") (pin "1") (pinfunction "1_1") (pintype "bidirectional"))
      (node (ref "C27") (pin "1") (pinfunction "1_1") (pintype "passive"))
      (node (ref "C29") (pin "1") (pinfunction "1_1") (pintype "passive"))
      (node (ref "C3") (pin "1") (pinfunction "1_1") (pintype "passive"))
      (node (ref "C30") (pin "1") (pinfunction "1_1") (pintype "passive"))
      (node (ref "C32") (pin "1") (pinfunction "1_1") (pintype "passive"))
      (node (ref "C4") (pin "1") (pinfunction "1_1") (pintype "passive"))
      (node (ref "COUT6") (pin "2") (pinfunction "2_2") (pintype "passive"))
      (node (ref "D4") (pin "1") (pinfunction "K_1") (pintype "bidirectional"))
      (node (ref "IC3") (pin "13") (pinfunction "VDD_13") (pintype "bidirectional"))
      (node (ref "IC3") (pin "8") (pinfunction "VDDIO_8") (pintype "bidirectional"))
      (node (ref "L6") (pin "2") (pinfunction "2_2") (pintype "bidirectional"))
      (node (ref "Q1") (pin "1") (pinfunction "C_1") (pintype "passive"))
      (node (ref "Q2") (pin "1") (pinfunction "C_1") (pintype "passive"))
      (node (ref "Q3") (pin "1") (pinfunction "C_1") (pintype "passive"))
      (node (ref "Q4") (pin "1") (pinfunction "C_1") (pintype "passive"))
      (node (ref "Q5") (pin "1") (pinfunction "C_1") (pintype "passive"))
      (node (ref "Q6") (pin "1") (pinfunction "C_1") (pintype "passive"))
      (node (ref "Q7") (pin "1") (pinfunction "C_1") (pintype "passive"))
      (node (ref "R2") (pin "2") (pinfunction "2_2") (pintype "passive"))
      (node (ref "R22") (pin "2") (pinfunction "2_2") (pintype "passive"))
      (node (ref "R29") (pin "2") (pinfunction "2_2") (pintype "passive"))
      (node (ref "R3") (pin "2") (pinfunction "2_2") (pintype "passive"))
      (node (ref "R30") (pin "2") (pinfunction "2_2") (pintype "passive"))
      (node (ref "R31") (pin "2") (pinfunction "2_2") (pintype "passive"))
      (node (ref "R35") (pin "2") (pinfunction "2_2") (pintype "passive"))
      (node (ref "R36") (pin "2") (pinfunction "2_2") (pintype "passive"))
      (node (ref "R52") (pin "2") (pinfunction "2_2") (pintype "passive"))
      (node (ref "R53") (pin "2") (pinfunction "2_2") (pintype "passive"))
      (node (ref "RFBT5") (pin "1") (pinfunction "1_1") (pintype "passive"))
      (node (ref "U$8") (pin "11") (pinfunction "BS1_11") (pintype "bidirectional"))
      (node (ref "U$8") (pin "6") (pinfunction "VBAT_6") (pintype "bidirectional"))
      (node (ref "U$8") (pin "9") (pinfunction "VDD_9") (pintype "bidirectional"))
      (node (ref "U1") (pin "2") (pinfunction "3V3_2") (pintype "bidirectional"))
      (node (ref "UART") (pin "1") (pinfunction "1_1") (pintype "passive"))
    )
    (net (code "3") (name "5V") (class "Default")
      (node (ref "C17") (pin "1") (pinfunction "1_1") (pintype "passive"))
      (node (ref "C18") (pin "1") (pinfunction "1_1") (pintype "passive"))
      (node (ref "COUT5") (pin "1") (pinfunction "1_1") (pintype "passive"))
      (node (ref "J5") (pin "3") (pinfunction "3_3") (pintype "bidirectional"))
      (node (ref "J6") (pin "3") (pinfunction "3_3") (pintype "bidirectional"))
      (node (ref "L5") (pin "1") (pinfunction "1_1") (pintype "bidirectional"))
      (node (ref "LED5") (pin "2") (pinfunction "A_2") (pintype "bidirectional"))
      (node (ref "RFTB5") (pin "2") (pinfunction "2_2") (pintype "passive"))
    )
    (net (code "4") (name "5V_FAN") (class "Default")
      (node (ref "C39") (pin "1") (pinfunction "1_1") (pintype "passive"))
      (node (ref "CIN3") (pin "1") (pinfunction "1_1") (pintype "passive"))
      (node (ref "D6") (pin "1") (pinfunction "K_1") (pintype "bidirectional"))
      (node (ref "J7") (pin "P$1") (pinfunction "P$1_P$1") (pintype "bidirectional"))
      (node (ref "L7") (pin "1") (pinfunction "1_1") (pintype "bidirectional"))
      (node (ref "RFBT6") (pin "2") (pinfunction "2_2") (pintype "passive"))
    )
    (net (code "5") (name "CB1") (class "Default")
      (node (ref "CBST1") (pin "1") (pinfunction "1_1") (pintype "passive"))
      (node (ref "PS2") (pin "1") (pinfunction "CB1_1") (pintype "output"))
    )
    (net (code "6") (name "CB2") (class "Default")
      (node (ref "CBST2") (pin "1") (pinfunction "1_1") (pintype "passive"))
      (node (ref "PS2") (pin "12") (pinfunction "CB2_12") (pintype "output"))
    )
    (net (code "7") (name "CB3") (class "Default")
      (node (ref "CBST3") (pin "2") (pinfunction "2_2") (pintype "passive"))
      (node (ref "PS2") (pin "28") (pinfunction "CB3_28") (pintype "output"))
    )
    (net (code "8") (name "CB4") (class "Default")
      (node (ref "CBST4") (pin "2") (pinfunction "2_2") (pintype "passive"))
      (node (ref "PS2") (pin "33") (pinfunction "CB4_33") (pintype "output"))
    )
    (net (code "9") (name "CS") (class "Default")
      (node (ref "IC3") (pin "22") (pinfunction "NCS_22") (pintype "bidirectional"))
      (node (ref "U1") (pin "11") (pinfunction "IO26_11") (pintype "bidirectional"))
    )
    (net (code "10") (name "EN") (class "Default")
      (node (ref "C28") (pin "1") (pinfunction "1_1") (pintype "passive"))
      (node (ref "R31") (pin "1") (pinfunction "1_1") (pintype "passive"))
      (node (ref "R38") (pin "2") (pinfunction "2_2") (pintype "passive"))
      (node (ref "U1") (pin "3") (pinfunction "EN_3") (pintype "bidirectional"))
    )
    (net (code "11") (name "FANPWM{slash}TMS") (class "Default")
      (node (ref "J3") (pin "1") (pinfunction "1_1") (pintype "passive"))
      (node (ref "J8") (pin "2") (pinfunction "2_2") (pintype "passive"))
      (node (ref "U1") (pin "13") (pinfunction "IO14_13") (pintype "bidirectional"))
    )
    (net (code "12") (name "FSYNC") (class "Default")
      (node (ref "IC3") (pin "11") (pinfunction "FSYNC_11") (pintype "bidirectional"))
    )
    (net (code "13") (name "F_RECEIVER") (class "Default")
      (node (ref "Q1") (pin "2") (pinfunction "E_2") (pintype "passive"))
      (node (ref "R14") (pin "2") (pinfunction "2_2") (pintype "passive"))
      (node (ref "U1") (pin "20") (pinfunction "CLK_20") (pintype "bidirectional"))
    )
    (net (code "14") (name "GND") (class "Default")
      (node (ref "C10") (pin "2") (pinfunction "2_2") (pintype "passive"))
      (node (ref "C11") (pin "2") (pinfunction "2_2") (pintype "passive"))
      (node (ref "C12") (pin "2") (pinfunction "2_2") (pintype "passive"))
      (node (ref "C13") (pin "2") (pinfunction "2_2") (pintype "passive"))
      (node (ref "C14") (pin "2") (pinfunction "2_2") (pintype "passive"))
      (node (ref "C15") (pin "2") (pinfunction "2_2") (pintype "passive"))
      (node (ref "C16") (pin "2") (pinfunction "2_2") (pintype "passive"))
      (node (ref "C17") (pin "2") (pinfunction "2_2") (pintype "passive"))
      (node (ref "C18") (pin "2") (pinfunction "2_2") (pintype "passive"))
      (node (ref "C19") (pin "2") (pinfunction "2_2") (pintype "passive"))
      (node (ref "C2") (pin "2") (pinfunction "2_2") (pintype "passive"))
      (node (ref "C20") (pin "2") (pinfunction "2_2") (pintype "passive"))
      (node (ref "C21") (pin "2") (pinfunction "2_2") (pintype "passive"))
      (node (ref "C22") (pin "2") (pinfunction "2_2") (pintype "passive"))
      (node (ref "C23") (pin "2") (pinfunction "2_2") (pintype "passive"))
      (node (ref "C24") (pin "2") (pinfunction "2_2") (pintype "passive"))
      (node (ref "C25") (pin "2") (pinfunction "2_2") (pintype "passive"))
      (node (ref "C26") (pin "2") (pinfunction "2_2") (pintype "bidirectional"))
      (node (ref "C27") (pin "2") (pinfunction "2_2") (pintype "passive"))
      (node (ref "C28") (pin "2") (pinfunction "2_2") (pintype "passive"))
      (node (ref "C29") (pin "2") (pinfunction "2_2") (pintype "passive"))
      (node (ref "C3") (pin "2") (pinfunction "2_2") (pintype "passive"))
      (node (ref "C30") (pin "2") (pinfunction "2_2") (pintype "passive"))
      (node (ref "C31") (pin "2") (pinfunction "2_2") (pintype "passive"))
      (node (ref "C32") (pin "2") (pinfunction "2_2") (pintype "passive"))
      (node (ref "C33") (pin "2") (pinfunction "2_2") (pintype "passive"))
      (node (ref "C34") (pin "2") (pinfunction "2_2") (pintype "passive"))
      (node (ref "C35") (pin "2") (pinfunction "2_2") (pintype "passive"))
      (node (ref "C36") (pin "2") (pinfunction "2_2") (pintype "passive"))
      (node (ref "C37") (pin "2") (pinfunction "2_2") (pintype "passive"))
      (node (ref "C38") (pin "2") (pinfunction "2_2") (pintype "passive"))
      (node (ref "C39") (pin "2") (pinfunction "2_2") (pintype "passive"))
      (node (ref "C4") (pin "2") (pinfunction "2_2") (pintype "passive"))
      (node (ref "C40") (pin "2") (pinfunction "2_2") (pintype "passive"))
      (node (ref "C43") (pin "1") (pinfunction "1_1") (pintype "passive"))
      (node (ref "C44") (pin "1") (pinfunction "1_1") (pintype "passive"))
      (node (ref "C45") (pin "2") (pinfunction "2_2") (pintype "passive"))
      (node (ref "C46") (pin "2") (pinfunction "2_2") (pintype "passive"))
      (node (ref "C47") (pin "2") (pinfunction "2_2") (pintype "passive"))
      (node (ref "C48") (pin "2") (pinfunction "2_2") (pintype "passive"))
      (node (ref "C49") (pin "2") (pinfunction "2_2") (pintype "passive"))
      (node (ref "C5") (pin "2") (pinfunction "2_2") (pintype "passive"))
      (node (ref "C50") (pin "2") (pinfunction "2_2") (pintype "passive"))
      (node (ref "C6") (pin "2") (pinfunction "2_2") (pintype "passive"))
      (node (ref "C7") (pin "2") (pinfunction "2_2") (pintype "passive"))
      (node (ref "C8") (pin "1") (pinfunction "1_1") (pintype "passive"))
      (node (ref "C9") (pin "2") (pinfunction "2_2") (pintype "passive"))
      (node (ref "CCOMP10") (pin "2") (pinfunction "2_2") (pintype "passive"))
      (node (ref "CCOMP11") (pin "1") (pinfunction "1_1") (pintype "passive"))
      (node (ref "CCOMP13") (pin "1") (pinfunction "1_1") (pintype "passive"))
      (node (ref "CCOMP5") (pin "2") (pinfunction "2_2") (pintype "passive"))
      (node (ref "CCOMP6") (pin "2") (pinfunction "2_2") (pintype "passive"))
      (node (ref "CCOMP7") (pin "2") (pinfunction "2_2") (pintype "passive"))
      (node (ref "CCOMP8") (pin "1") (pinfunction "1_1") (pintype "passive"))
      (node (ref "CCOMP9") (pin "1") (pinfunction "1_1") (pintype "passive"))
      (node (ref "CIN1") (pin "2") (pinfunction "2_2") (pintype "passive"))
      (node (ref "CIN2") (pin "2") (pinfunction "2_2") (pintype "passive"))
      (node (ref "CIN3") (pin "2") (pinfunction "2_2") (pintype "passive"))
      (node (ref "COUT1") (pin "2") (pinfunction "2_2") (pintype "passive"))
      (node (ref "COUT5") (pin "2") (pinfunction "2_2") (pintype "passive"))
      (node (ref "COUT6") (pin "1") (pinfunction "1_1") (pintype "passive"))
      (node (ref "CSS5") (pin "2") (pinfunction "2_2") (pintype "passive"))
      (node (ref "CSS6") (pin "2") (pinfunction "2_2") (pintype "passive"))
      (node (ref "CSS7") (pin "2") (pinfunction "2_2") (pintype "passive"))
      (node (ref "CSS8") (pin "1") (pinfunction "1_1") (pintype "passive"))
      (node (ref "CVDD1") (pin "2") (pinfunction "2_2") (pintype "passive"))
      (node (ref "CVDDA1") (pin "1") (pinfunction "1_1") (pintype "passive"))
      (node (ref "CVDDG1") (pin "2") (pinfunction "2_2") (pintype "passive"))
      (node (ref "IC1") (pin "11") (pinfunction "NC_1_11") (pintype "bidirectional"))
      (node (ref "IC1") (pin "12") (pinfunction "NC_2_12") (pintype "bidirectional"))
      (node (ref "IC1") (pin "20") (pinfunction "AGND_20") (pintype "bidirectional"))
      (node (ref "IC1") (pin "21") (pinfunction "PGND_21") (pintype "bidirectional"))
      (node (ref "IC3") (pin "18") (pinfunction "GND_18") (pintype "bidirectional"))
      (node (ref "IC3") (pin "25") (pinfunction "PAD_25") (pintype "bidirectional"))
      (node (ref "IC6") (pin "3") (pinfunction "GND_3") (pintype "bidirectional"))
      (node (ref "IC8") (pin "3") (pinfunction "GND_3") (pintype "bidirectional"))
      (node (ref "IC9") (pin "4") (pinfunction "INB_4") (pintype "bidirectional"))
      (node (ref "J2") (pin "P$2") (pinfunction "P$2_P$2") (pintype "bidirectional"))
      (node (ref "J5") (pin "4") (pinfunction "4_4") (pintype "bidirectional"))
      (node (ref "J6") (pin "4") (pinfunction "4_4") (pintype "bidirectional"))
      (node (ref "PB1") (pin "1") (pinfunction "1_1") (pintype "passive"))
      (node (ref "PB2") (pin "1") (pinfunction "1_1") (pintype "passive"))
      (node (ref "PS2") (pin "21") (pinfunction "AGND_21") (pintype "power_in"))
      (node (ref "PS2") (pin "49") (pinfunction "PGND_49") (pintype "power_in"))
      (node (ref "PS2") (pin "7") (pinfunction "PGND1_7") (pintype "power_in"))
      (node (ref "PS2") (pin "8") (pinfunction "PGND2_8") (pintype "power_in"))
      (node (ref "Q10") (pin "3") (pinfunction "N1S/N2S_3") (pintype "bidirectional"))
      (node (ref "Q11") (pin "3") (pinfunction "N1S/N2S_3") (pintype "bidirectional"))
      (node (ref "R1") (pin "1") (pinfunction "1_1") (pintype "passive"))
      (node (ref "R11") (pin "1") (pinfunction "1_1") (pintype "passive"))
      (node (ref "R13") (pin "1") (pinfunction "1_1") (pintype "passive"))
      (node (ref "R14") (pin "1") (pinfunction "1_1") (pintype "passive"))
      (node (ref "R15") (pin "1") (pinfunction "1_1") (pintype "passive"))
      (node (ref "R16") (pin "1") (pinfunction "1_1") (pintype "passive"))
      (node (ref "R17") (pin "1") (pinfunction "1_1") (pintype "passive"))
      (node (ref "R18") (pin "1") (pinfunction "1_1") (pintype "passive"))
      (node (ref "R19") (pin "1") (pinfunction "1_1") (pintype "passive"))
      (node (ref "R20") (pin "1") (pinfunction "1_1") (pintype "passive"))
      (node (ref "R23") (pin "1") (pinfunction "1_1") (pintype "passive"))
      (node (ref "R24") (pin "1") (pinfunction "1_1") (pintype "passive"))
      (node (ref "R26") (pin "1") (pinfunction "1_1") (pintype "passive"))
      (node (ref "R45") (pin "1") (pinfunction "1_1") (pintype "passive"))
      (node (ref "R6") (pin "1") (pinfunction "1_1") (pintype "passive"))
      (node (ref "R8") (pin "1") (pinfunction "1_1") (pintype "passive"))
      (node (ref "R9") (pin "1") (pinfunction "1_1") (pintype "passive"))
      (node (ref "RFBB5") (pin "1") (pinfunction "1_1") (pintype "passive"))
      (node (ref "RFBB6") (pin "1") (pinfunction "1_1") (pintype "passive"))
      (node (ref "RFBB7") (pin "2") (pinfunction "2_2") (pintype "passive"))
      (node (ref "RFBB8") (pin "1") (pinfunction "1_1") (pintype "passive"))
      (node (ref "ROSC1") (pin "1") (pinfunction "1_1") (pintype "passive"))
      (node (ref "RPMU7") (pin "2") (pinfunction "2_2") (pintype "passive"))
      (node (ref "T1") (pin "1") (pinfunction "S_1") (pintype "passive"))
      (node (ref "T1") (pin "2") (pinfunction "S_2") (pintype "passive"))
      (node (ref "T1") (pin "3") (pinfunction "S_3") (pintype "passive"))
      (node (ref "T2") (pin "2") (pinfunction "E_2") (pintype "passive"))
      (node (ref "T3") (pin "2") (pinfunction "E_2") (pintype "passive"))
      (node (ref "T4") (pin "S") (pinfunction "S_S") (pintype "passive"))
      (node (ref "T5") (pin "S") (pinfunction "S_S") (pintype "passive"))
      (node (ref "T6") (pin "S") (pinfunction "S_S") (pintype "passive"))
      (node (ref "T7") (pin "S") (pinfunction "S_S") (pintype "passive"))
      (node (ref "T8") (pin "S") (pinfunction "S_S") (pintype "passive"))
      (node (ref "U$8") (pin "1") (pinfunction "NC_1_1") (pintype "bidirectional"))
      (node (ref "U$8") (pin "10") (pinfunction "BS0_10") (pintype "bidirectional"))
      (node (ref "U$8") (pin "12") (pinfunction "BS2_12") (pintype "bidirectional"))
      (node (ref "U$8") (pin "13") (pinfunction "CS#_13") (pintype "bidirectional"))
      (node (ref "U$8") (pin "16") (pinfunction "R/W#_16") (pintype "bidirectional"))
      (node (ref "U$8") (pin "17") (pinfunction "E/RD#_17") (pintype "bidirectional"))
      (node (ref "U$8") (pin "21") (pinfunction "D3_21") (pintype "bidirectional"))
      (node (ref "U$8") (pin "22") (pinfunction "D4_22") (pintype "bidirectional"))
      (node (ref "U$8") (pin "23") (pinfunction "D5_23") (pintype "bidirectional"))
      (node (ref "U$8") (pin "24") (pinfunction "D6_24") (pintype "bidirectional"))
      (node (ref "U$8") (pin "25") (pinfunction "D7_25") (pintype "bidirectional"))
      (node (ref "U$8") (pin "29") (pinfunction "VLSS_29") (pintype "bidirectional"))
      (node (ref "U$8") (pin "30") (pinfunction "NC_3_30") (pintype "bidirectional"))
      (node (ref "U$8") (pin "8") (pinfunction "VSS_8") (pintype "bidirectional"))
      (node (ref "U1") (pin "1") (pinfunction "GND_1") (pintype "bidirectional"))
      (node (ref "U1") (pin "15") (pinfunction "GND_15") (pintype "bidirectional"))
      (node (ref "U1") (pin "38") (pinfunction "GND_38") (pintype "bidirectional"))
      (node (ref "U1") (pin "GND") (pinfunction "GND_GND") (pintype "bidirectional"))
      (node (ref "UART") (pin "2") (pinfunction "2_2") (pintype "passive"))
    )
    (net (code "15") (name "I2CALERT") (class "Default")
      (node (ref "PS2") (pin "41") (pinfunction "I2CALERT_41") (pintype "output"))
      (node (ref "RPMU8") (pin "1") (pinfunction "1_1") (pintype "passive"))
    )
    (net (code "16") (name "INT") (class "Default")
      (node (ref "IC3") (pin "12") (pinfunction "INT_12") (pintype "bidirectional"))
    )
    (net (code "17") (name "IO0") (class "Default")
      (node (ref "R22") (pin "1") (pinfunction "1_1") (pintype "passive"))
      (node (ref "R37") (pin "2") (pinfunction "2_2") (pintype "passive"))
      (node (ref "U1") (pin "25") (pinfunction "IO0_25") (pintype "bidirectional"))
    )
    (net (code "18") (name "IO2") (class "Default")
      (node (ref "R23") (pin "2") (pinfunction "2_2") (pintype "passive"))
      (node (ref "U1") (pin "24") (pinfunction "IO2_24") (pintype "bidirectional"))
    )
    (net (code "19") (name "LF_EMITTER{slash}TCK") (class "Default")
      (node (ref "JTAG") (pin "2") (pinfunction "2_2") (pintype "passive"))
      (node (ref "R11") (pin "2") (pinfunction "2_2") (pintype "passive"))
      (node (ref "T5") (pin "G") (pinfunction "G_G") (pintype "passive"))
      (node (ref "U1") (pin "16") (pinfunction "IO13_16") (pintype "bidirectional"))
    )
    (net (code "20") (name "LF_RECEIVER") (class "Default")
      (node (ref "Q4") (pin "2") (pinfunction "E_2") (pintype "passive"))
      (node (ref "R17") (pin "2") (pinfunction "2_2") (pintype "passive"))
      (node (ref "U1") (pin "26") (pinfunction "IO4_26") (pintype "bidirectional"))
    )
    (net (code "21") (name "LPWMA") (class "Default")
      (node (ref "IC8") (pin "2") (pinfunction "INA_2") (pintype "bidirectional"))
      (node (ref "R52") (pin "1") (pinfunction "1_1") (pintype "passive"))
      (node (ref "U1") (pin "31") (pinfunction "IO19_31") (pintype "bidirectional"))
    )
    (net (code "22") (name "LPWMB") (class "Default")
      (node (ref "IC8") (pin "4") (pinfunction "INB_4") (pintype "bidirectional"))
      (node (ref "R53") (pin "1") (pinfunction "1_1") (pintype "passive"))
      (node (ref "U1") (pin "30") (pinfunction "IO18_30") (pintype "bidirectional"))
    )
    (net (code "23") (name "L_EMITTER") (class "Default")
      (node (ref "R8") (pin "2") (pinfunction "2_2") (pintype "passive"))
      (node (ref "T4") (pin "G") (pinfunction "G_G") (pintype "passive"))
      (node (ref "U1") (pin "36") (pinfunction "IO22_36") (pintype "bidirectional"))
    )
    (net (code "24") (name "L_ENC_A") (class "Default")
      (node (ref "J6") (pin "1") (pinfunction "1_1") (pintype "bidirectional"))
      (node (ref "U1") (pin "5") (pinfunction "SENSOR_VN_5") (pintype "input"))
    )
    (net (code "25") (name "L_ENC_B") (class "Default")
      (node (ref "J6") (pin "2") (pinfunction "2_2") (pintype "bidirectional"))
      (node (ref "U1") (pin "4") (pinfunction "SENSOR_VP_4") (pintype "input"))
    )
    (net (code "26") (name "L_RECEIVER1") (class "Default")
      (node (ref "Q2") (pin "2") (pinfunction "E_2") (pintype "passive"))
      (node (ref "R15") (pin "2") (pinfunction "2_2") (pintype "passive"))
      (node (ref "U1") (pin "22") (pinfunction "SD1_22") (pintype "bidirectional"))
    )
    (net (code "27") (name "L_RECEIVER2") (class "Default")
      (node (ref "Q3") (pin "2") (pinfunction "E_2") (pintype "passive"))
      (node (ref "R16") (pin "2") (pinfunction "2_2") (pintype "passive"))
      (node (ref "U1") (pin "21") (pinfunction "SDO_21") (pintype "bidirectional"))
    )
    (net (code "28") (name "M_EMITTER{slash}TDO") (class "Default")
      (node (ref "JTAG") (pin "1") (pinfunction "1_1") (pintype "passive"))
      (node (ref "R13") (pin "2") (pinfunction "2_2") (pintype "passive"))
      (node (ref "T6") (pin "G") (pinfunction "G_G") (pintype "passive"))
      (node (ref "U1") (pin "23") (pinfunction "IO15_23") (pintype "bidirectional"))
    )
    (net (code "29") (name "Net-(C2-Pad1)") (class "Default")
      (node (ref "C2") (pin "1") (pinfunction "1_1") (pintype "passive"))
      (node (ref "R21") (pin "1") (pinfunction "1_1") (pintype "passive"))
    )
    (net (code "30") (name "Net-(C43-Pad2)") (class "Default")
      (node (ref "C43") (pin "2") (pinfunction "2_2") (pintype "passive"))
      (node (ref "PB1") (pin "2") (pinfunction "2_2") (pintype "passive"))
      (node (ref "R37") (pin "1") (pinfunction "1_1") (pintype "passive"))
    )
    (net (code "31") (name "Net-(C44-Pad2)") (class "Default")
      (node (ref "C44") (pin "2") (pinfunction "2_2") (pintype "passive"))
      (node (ref "PB2") (pin "2") (pinfunction "2_2") (pintype "passive"))
      (node (ref "R38") (pin "1") (pinfunction "1_1") (pintype "passive"))
    )
    (net (code "32") (name "Net-(CCOMP6-Pad1)") (class "Default")
      (node (ref "CCOMP6") (pin "1") (pinfunction "1_1") (pintype "passive"))
      (node (ref "RCOMP7") (pin "1") (pinfunction "1_1") (pintype "passive"))
    )
    (net (code "33") (name "Net-(CCOMP8-Pad2)") (class "Default")
      (node (ref "CCOMP8") (pin "2") (pinfunction "2_2") (pintype "passive"))
      (node (ref "RCOMP6") (pin "1") (pinfunction "1_1") (pintype "passive"))
    )
    (net (code "34") (name "Net-(CCOMP9-Pad2)") (class "Default")
      (node (ref "CCOMP9") (pin "2") (pinfunction "2_2") (pintype "passive"))
      (node (ref "RCOMP8") (pin "2") (pinfunction "2_2") (pintype "passive"))
    )
    (net (code "35") (name "Net-(CCOMP11-Pad2)") (class "Default")
      (node (ref "CCOMP11") (pin "2") (pinfunction "2_2") (pintype "passive"))
      (node (ref "RCOMP5") (pin "2") (pinfunction "2_2") (pintype "passive"))
    )
    (net (code "36") (name "Net-(D3-PadC)") (class "Default")
      (node (ref "D3") (pin "C") (pinfunction "C_C") (pintype "passive"))
      (node (ref "R48") (pin "2") (pinfunction "2_2") (pintype "passive"))
    )
    (net (code "37") (name "Net-(D4-A)") (class "Default")
      (node (ref "D4") (pin "2") (pinfunction "A_2") (pintype "bidirectional"))
      (node (ref "R35") (pin "1") (pinfunction "1_1") (pintype "passive"))
      (node (ref "U$8") (pin "14") (pinfunction "RES#_14") (pintype "bidirectional"))
    )
    (net (code "38") (name "Net-(D5-PadC)") (class "Default")
      (node (ref "D5") (pin "C") (pinfunction "C_C") (pintype "passive"))
      (node (ref "R49") (pin "2") (pinfunction "2_2") (pintype "passive"))
    )
    (net (code "39") (name "Net-(D6-A)") (class "Default")
      (node (ref "D6") (pin "2") (pinfunction "A_2") (pintype "bidirectional"))
      (node (ref "J7") (pin "P$2") (pinfunction "P$2_P$2") (pintype "bidirectional"))
      (node (ref "T1") (pin "MB") (pinfunction "D_MB") (pintype "passive"))
    )
    (net (code "40") (name "Net-(IC1-BOOT)") (class "Default")
      (node (ref "C1") (pin "1") (pinfunction "1_1") (pintype "passive"))
      (node (ref "IC1") (pin "8") (pinfunction "BOOT_8") (pintype "bidirectional"))
    )
    (net (code "41") (name "Net-(IC1-COMP)") (class "Default")
      (node (ref "C5") (pin "1") (pinfunction "1_1") (pintype "passive"))
      (node (ref "IC1") (pin "18") (pinfunction "COMP_18") (pintype "bidirectional"))
      (node (ref "R21") (pin "2") (pinfunction "2_2") (pintype "passive"))
    )
    (net (code "42") (name "Net-(IC1-FB)") (class "Default")
      (node (ref "IC1") (pin "17") (pinfunction "FB_17") (pintype "bidirectional"))
      (node (ref "R24") (pin "2") (pinfunction "2_2") (pintype "passive"))
      (node (ref "R25") (pin "1") (pinfunction "1_1") (pintype "passive"))
    )
    (net (code "43") (name "Net-(IC1-FSW)") (class "Default")
      (node (ref "IC1") (pin "3") (pinfunction "FSW_3") (pintype "bidirectional"))
      (node (ref "R27") (pin "1") (pinfunction "1_1") (pintype "passive"))
    )
    (net (code "44") (name "Net-(IC1-ILIM)") (class "Default")
      (node (ref "IC1") (pin "19") (pinfunction "ILIM_19") (pintype "bidirectional"))
      (node (ref "R26") (pin "2") (pinfunction "2_2") (pintype "passive"))
    )
    (net (code "45") (name "Net-(IC1-SS)") (class "Default")
      (node (ref "C47") (pin "1") (pinfunction "1_1") (pintype "passive"))
      (node (ref "IC1") (pin "10") (pinfunction "SS_10") (pintype "bidirectional"))
    )
    (net (code "46") (name "Net-(IC1-SW_1)") (class "Default")
      (node (ref "C1") (pin "2") (pinfunction "2_2") (pintype "passive"))
      (node (ref "IC1") (pin "4") (pinfunction "SW_1_4") (pintype "bidirectional"))
      (node (ref "IC1") (pin "5") (pinfunction "SW_2_5") (pintype "bidirectional"))
      (node (ref "IC1") (pin "6") (pinfunction "SW_3_6") (pintype "bidirectional"))
      (node (ref "IC1") (pin "7") (pinfunction "SW_4_7") (pintype "bidirectional"))
      (node (ref "R27") (pin "2") (pinfunction "2_2") (pintype "passive"))
      (node (ref "U$9") (pin "P$2") (pinfunction "2_P$2") (pintype "bidirectional"))
    )
    (net (code "47") (name "Net-(IC1-VCC)") (class "Default")
      (node (ref "C48") (pin "1") (pinfunction "1_1") (pintype "passive"))
      (node (ref "IC1") (pin "1") (pinfunction "VCC_1") (pintype "bidirectional"))
    )
    (net (code "48") (name "Net-(IC3-REGOUT)") (class "Default")
      (node (ref "C31") (pin "1") (pinfunction "1_1") (pintype "passive"))
      (node (ref "IC3") (pin "10") (pinfunction "REGOUT_10") (pintype "bidirectional"))
    )
    (net (code "49") (name "Net-(IC6-OUTA)") (class "Default")
      (node (ref "IC6") (pin "7") (pinfunction "OUTA_7") (pintype "bidirectional"))
      (node (ref "Q10") (pin "1") (pinfunction "N1G_1") (pintype "bidirectional"))
      (node (ref "Q10") (pin "8") (pinfunction "P1G_8") (pintype "bidirectional"))
    )
    (net (code "50") (name "Net-(IC6-OUTB)") (class "Default")
      (node (ref "IC6") (pin "5") (pinfunction "OUTB_5") (pintype "bidirectional"))
      (node (ref "Q10") (pin "4") (pinfunction "N2G_4") (pintype "bidirectional"))
      (node (ref "Q10") (pin "5") (pinfunction "P2G_5") (pintype "bidirectional"))
    )
    (net (code "51") (name "Net-(IC8-OUTA)") (class "Default")
      (node (ref "IC8") (pin "7") (pinfunction "OUTA_7") (pintype "bidirectional"))
      (node (ref "Q11") (pin "1") (pinfunction "N1G_1") (pintype "bidirectional"))
      (node (ref "Q11") (pin "8") (pinfunction "P1G_8") (pintype "bidirectional"))
    )
    (net (code "52") (name "Net-(IC8-OUTB)") (class "Default")
      (node (ref "IC8") (pin "5") (pinfunction "OUTB_5") (pintype "bidirectional"))
      (node (ref "Q11") (pin "4") (pinfunction "N2G_4") (pintype "bidirectional"))
      (node (ref "Q11") (pin "5") (pinfunction "P2G_5") (pintype "bidirectional"))
    )
    (net (code "53") (name "Net-(IC9-GND)") (class "Default")
      (node (ref "IC9") (pin "3") (pinfunction "GND_3") (pintype "bidirectional"))
      (node (ref "J8") (pin "1") (pinfunction "1_1") (pintype "passive"))
      (node (ref "R36") (pin "1") (pinfunction "1_1") (pintype "passive"))
    )
    (net (code "54") (name "Net-(IC9-VDD)") (class "Default")
      (node (ref "IC9") (pin "6") (pinfunction "VDD_6") (pintype "bidirectional"))
      (node (ref "T1") (pin "4") (pinfunction "G_4") (pintype "passive"))
    )
    (net (code "55") (name "Net-(LED1-K)") (class "Default")
      (node (ref "LED1") (pin "1") (pinfunction "K_1") (pintype "bidirectional"))
      (node (ref "R4") (pin "2") (pinfunction "2_2") (pintype "passive"))
    )
    (net (code "56") (name "Net-(LED2-K)") (class "Default")
      (node (ref "LED2") (pin "1") (pinfunction "K_1") (pintype "bidirectional"))
      (node (ref "R5") (pin "2") (pinfunction "2_2") (pintype "passive"))
    )
    (net (code "57") (name "Net-(LED3-K)") (class "Default")
      (node (ref "LED3") (pin "1") (pinfunction "K_1") (pintype "bidirectional"))
      (node (ref "R7") (pin "2") (pinfunction "2_2") (pintype "passive"))
    )
    (net (code "58") (name "Net-(LED4-K)") (class "Default")
      (node (ref "LED4") (pin "1") (pinfunction "K_1") (pintype "bidirectional"))
      (node (ref "R10") (pin "2") (pinfunction "2_2") (pintype "passive"))
    )
    (net (code "59") (name "Net-(LED5-K)") (class "Default")
      (node (ref "LED5") (pin "1") (pinfunction "K_1") (pintype "bidirectional"))
      (node (ref "LED7") (pin "2") (pinfunction "A_2") (pintype "bidirectional"))
    )
    (net (code "60") (name "Net-(LED7-K)") (class "Default")
      (node (ref "LED7") (pin "1") (pinfunction "K_1") (pintype "bidirectional"))
      (node (ref "R12") (pin "2") (pinfunction "2_2") (pintype "passive"))
    )
    (net (code "61") (name "Net-(PLZ6V2B-G3/H-PadA)") (class "Default")
      (node (ref "PLZ6V2B-G3/H") (pin "A") (pinfunction "A_A") (pintype "bidirectional"))
      (node (ref "R45") (pin "2") (pinfunction "2_2") (pintype "passive"))
      (node (ref "R46") (pin "1") (pinfunction "1_1") (pintype "passive"))
    )
    (net (code "62") (name "Net-(PS2-COMP1)") (class "Default")
      (node (ref "CCOMP13") (pin "2") (pinfunction "2_2") (pintype "passive"))
      (node (ref "PS2") (pin "46") (pinfunction "COMP1_46") (pintype "input"))
      (node (ref "RCOMP5") (pin "1") (pinfunction "1_1") (pintype "passive"))
    )
    (net (code "63") (name "Net-(PS2-COMP2)") (class "Default")
      (node (ref "CCOMP5") (pin "1") (pinfunction "1_1") (pintype "passive"))
      (node (ref "PS2") (pin "15") (pinfunction "COMP2_15") (pintype "input"))
      (node (ref "RCOMP6") (pin "2") (pinfunction "2_2") (pintype "passive"))
    )
    (net (code "64") (name "Net-(PS2-COMP3)") (class "Default")
      (node (ref "CCOMP7") (pin "1") (pinfunction "1_1") (pintype "passive"))
      (node (ref "PS2") (pin "25") (pinfunction "COMP3_25") (pintype "input"))
      (node (ref "RCOMP7") (pin "2") (pinfunction "2_2") (pintype "passive"))
    )
    (net (code "65") (name "Net-(PS2-COMP4)") (class "Default")
      (node (ref "CCOMP10") (pin "1") (pinfunction "1_1") (pintype "passive"))
      (node (ref "PS2") (pin "36") (pinfunction "COMP4_36") (pintype "input"))
      (node (ref "RCOMP8") (pin "1") (pinfunction "1_1") (pintype "passive"))
    )
    (net (code "66") (name "Net-(PS2-I2CADDR)") (class "Default")
      (node (ref "PS2") (pin "38") (pinfunction "I2CADDR_38") (pintype "input"))
      (node (ref "RPMU7") (pin "1") (pinfunction "1_1") (pintype "passive"))
    )
    (net (code "67") (name "Net-(PS2-RCLOCK)") (class "Default")
      (node (ref "PS2") (pin "40") (pinfunction "RCLOCK_40") (pintype "input"))
      (node (ref "ROSC1") (pin "2") (pinfunction "2_2") (pintype "passive"))
    )
    (net (code "68") (name "Net-(PS2-SS1{slash}PG1)") (class "Default")
      (node (ref "CSS8") (pin "2") (pinfunction "2_2") (pintype "passive"))
      (node (ref "PS2") (pin "45") (pinfunction "SS1/PG1_45") (pintype "input"))
    )
    (net (code "69") (name "Net-(PS2-SS2{slash}PG2)") (class "Default")
      (node (ref "CSS5") (pin "1") (pinfunction "1_1") (pintype "passive"))
      (node (ref "PS2") (pin "16") (pinfunction "SS2/PG2_16") (pintype "input"))
    )
    (net (code "70") (name "Net-(PS2-SS3{slash}PG3)") (class "Default")
      (node (ref "CSS6") (pin "1") (pinfunction "1_1") (pintype "passive"))
      (node (ref "PS2") (pin "24") (pinfunction "SS3/PG3_24") (pintype "input"))
    )
    (net (code "71") (name "Net-(PS2-SS4{slash}PG4)") (class "Default")
      (node (ref "CSS7") (pin "1") (pinfunction "1_1") (pintype "passive"))
      (node (ref "PS2") (pin "37") (pinfunction "SS4/PG4_37") (pintype "input"))
    )
    (net (code "72") (name "Net-(PS2-SW1_1)") (class "Default")
      (node (ref "CBST1") (pin "2") (pinfunction "2_2") (pintype "passive"))
      (node (ref "L7") (pin "2") (pinfunction "2_2") (pintype "bidirectional"))
      (node (ref "PS2") (pin "2") (pinfunction "SW1_1_2") (pintype "output"))
      (node (ref "PS2") (pin "3") (pinfunction "SW1_2_3") (pintype "output"))
      (node (ref "PS2") (pin "4") (pinfunction "SW1_3_4") (pintype "output"))
    )
    (net (code "73") (name "Net-(PS2-VDDA)") (class "Default")
      (node (ref "CVDDA1") (pin "2") (pinfunction "2_2") (pintype "passive"))
      (node (ref "PS2") (pin "19") (pinfunction "VDDA_19") (pintype "output"))
    )
    (net (code "74") (name "Net-(PS2-VDDG)") (class "Default")
      (node (ref "CVDDG1") (pin "1") (pinfunction "1_1") (pintype "passive"))
      (node (ref "PS2") (pin "18") (pinfunction "VDDG_18") (pintype "input"))
    )
    (net (code "75") (name "Net-(PS2-VFB1)") (class "Default")
      (node (ref "PS2") (pin "47") (pinfunction "VFB1_47") (pintype "input"))
      (node (ref "RFBB8") (pin "2") (pinfunction "2_2") (pintype "passive"))
      (node (ref "RFBT6") (pin "1") (pinfunction "1_1") (pintype "passive"))
    )
    (net (code "76") (name "Net-(PS2-VFB2)") (class "Default")
      (node (ref "PS2") (pin "14") (pinfunction "VFB2_14") (pintype "input"))
      (node (ref "RFBB5") (pin "2") (pinfunction "2_2") (pintype "passive"))
      (node (ref "RFTB5") (pin "1") (pinfunction "1_1") (pintype "passive"))
    )
    (net (code "77") (name "Net-(PS2-VFB3)") (class "Default")
      (node (ref "PS2") (pin "26") (pinfunction "VFB3_26") (pintype "input"))
      (node (ref "RFBB6") (pin "2") (pinfunction "2_2") (pintype "passive"))
      (node (ref "RFBT8") (pin "1") (pinfunction "1_1") (pintype "passive"))
    )
    (net (code "78") (name "Net-(PS2-VFB4)") (class "Default")
      (node (ref "PS2") (pin "35") (pinfunction "VFB4_35") (pintype "input"))
      (node (ref "RFBB7") (pin "1") (pinfunction "1_1") (pintype "passive"))
      (node (ref "RFBT5") (pin "2") (pinfunction "2_2") (pintype "passive"))
    )
    (net (code "79") (name "Net-(Q10-N1D{slash}P1D)") (class "Default")
      (node (ref "J5") (pin "5") (pinfunction "5_5") (pintype "bidirectional"))
      (node (ref "Q10") (pin "2") (pinfunction "N1D/P1D_2") (pintype "bidirectional"))
    )
    (net (code "80") (name "Net-(Q10-N2D{slash}P2D)") (class "Default")
      (node (ref "J5") (pin "6") (pinfunction "6_6") (pintype "bidirectional"))
      (node (ref "Q10") (pin "6") (pinfunction "N2D/P2D_6") (pintype "bidirectional"))
    )
    (net (code "81") (name "Net-(Q11-N1D{slash}P1D)") (class "Default")
      (node (ref "J6") (pin "5") (pinfunction "5_5") (pintype "bidirectional"))
      (node (ref "Q11") (pin "2") (pinfunction "N1D/P1D_2") (pintype "bidirectional"))
    )
    (net (code "82") (name "Net-(Q11-N2D{slash}P2D)") (class "Default")
      (node (ref "J6") (pin "6") (pinfunction "6_6") (pintype "bidirectional"))
      (node (ref "Q11") (pin "6") (pinfunction "N2D/P2D_6") (pintype "bidirectional"))
    )
    (net (code "83") (name "Net-(R4-Pad1)") (class "Default")
      (node (ref "R4") (pin "1") (pinfunction "1_1") (pintype "passive"))
      (node (ref "T8") (pin "D") (pinfunction "D_D") (pintype "passive"))
    )
    (net (code "84") (name "Net-(R5-Pad1)") (class "Default")
      (node (ref "R5") (pin "1") (pinfunction "1_1") (pintype "passive"))
      (node (ref "T4") (pin "D") (pinfunction "D_D") (pintype "passive"))
    )
    (net (code "85") (name "Net-(R7-Pad1)") (class "Default")
      (node (ref "R7") (pin "1") (pinfunction "1_1") (pintype "passive"))
      (node (ref "T7") (pin "D") (pinfunction "D_D") (pintype "passive"))
    )
    (net (code "86") (name "Net-(R10-Pad1)") (class "Default")
      (node (ref "R10") (pin "1") (pinfunction "1_1") (pintype "passive"))
      (node (ref "T5") (pin "D") (pinfunction "D_D") (pintype "passive"))
    )
    (net (code "87") (name "Net-(R12-Pad1)") (class "Default")
      (node (ref "R12") (pin "1") (pinfunction "1_1") (pintype "passive"))
      (node (ref "T6") (pin "D") (pinfunction "D_D") (pintype "passive"))
    )
    (net (code "88") (name "Net-(T2-B)") (class "Default")
      (node (ref "R46") (pin "2") (pinfunction "2_2") (pintype "passive"))
      (node (ref "T2") (pin "1") (pinfunction "B_1") (pintype "passive"))
    )
    (net (code "89") (name "Net-(T2-C)") (class "Default")
      (node (ref "R47") (pin "1") (pinfunction "1_1") (pintype "passive"))
      (node (ref "R48") (pin "1") (pinfunction "1_1") (pintype "passive"))
      (node (ref "T2") (pin "3") (pinfunction "C_3") (pintype "passive"))
    )
    (net (code "90") (name "Net-(T3-B)") (class "Default")
      (node (ref "R47") (pin "2") (pinfunction "2_2") (pintype "passive"))
      (node (ref "T3") (pin "1") (pinfunction "B_1") (pintype "passive"))
    )
    (net (code "91") (name "Net-(T3-C)") (class "Default")
      (node (ref "R49") (pin "1") (pinfunction "1_1") (pintype "passive"))
      (node (ref "T3") (pin "3") (pinfunction "C_3") (pintype "passive"))
    )
    (net (code "92") (name "Net-(U$8-C1N)") (class "Default")
      (node (ref "C41") (pin "2") (pinfunction "2_2") (pintype "passive"))
      (node (ref "U$8") (pin "5") (pinfunction "C1N_5") (pintype "bidirectional"))
    )
    (net (code "93") (name "Net-(U$8-C1P)") (class "Default")
      (node (ref "C41") (pin "1") (pinfunction "1_1") (pintype "passive"))
      (node (ref "U$8") (pin "4") (pinfunction "C1P_4") (pintype "bidirectional"))
    )
    (net (code "94") (name "Net-(U$8-C2N)") (class "Default")
      (node (ref "C42") (pin "2") (pinfunction "2_2") (pintype "passive"))
      (node (ref "U$8") (pin "3") (pinfunction "C2N_3") (pintype "bidirectional"))
    )
    (net (code "95") (name "Net-(U$8-C2P)") (class "Default")
      (node (ref "C42") (pin "1") (pinfunction "1_1") (pintype "passive"))
      (node (ref "U$8") (pin "2") (pinfunction "C2P_2") (pintype "bidirectional"))
    )
    (net (code "96") (name "Net-(U$8-IREF)") (class "Default")
      (node (ref "R1") (pin "2") (pinfunction "2_2") (pintype "passive"))
      (node (ref "U$8") (pin "26") (pinfunction "IREF_26") (pintype "bidirectional"))
    )
    (net (code "97") (name "Net-(U$8-VCC)") (class "Default")
      (node (ref "C7") (pin "1") (pinfunction "1_1") (pintype "passive"))
      (node (ref "U$8") (pin "28") (pinfunction "VCC_28") (pintype "bidirectional"))
    )
    (net (code "98") (name "Net-(U$8-VCOMH)") (class "Default")
      (node (ref "C40") (pin "1") (pinfunction "1_1") (pintype "passive"))
      (node (ref "U$8") (pin "27") (pinfunction "VCOMH_27") (pintype "bidirectional"))
    )
    (net (code "99") (name "OUT2") (class "Default")
      (node (ref "CBST2") (pin "2") (pinfunction "2_2") (pintype "passive"))
      (node (ref "L5") (pin "2") (pinfunction "2_2") (pintype "bidirectional"))
      (node (ref "PS2") (pin "10") (pinfunction "SW2_2_10") (pintype "output"))
      (node (ref "PS2") (pin "11") (pinfunction "SW2_3_11") (pintype "output"))
      (node (ref "PS2") (pin "9") (pinfunction "SW2_1_9") (pintype "output"))
    )
    (net (code "100") (name "OUT3") (class "Default")
      (node (ref "CBST3") (pin "1") (pinfunction "1_1") (pintype "passive"))
      (node (ref "L8") (pin "1") (pinfunction "1_1") (pintype "bidirectional"))
      (node (ref "PS2") (pin "29") (pinfunction "SW3_29") (pintype "output"))
    )
    (net (code "101") (name "OUT4") (class "Default")
      (node (ref "CBST4") (pin "1") (pinfunction "1_1") (pintype "passive"))
      (node (ref "L6") (pin "1") (pinfunction "1_1") (pintype "bidirectional"))
      (node (ref "PS2") (pin "32") (pinfunction "SW4_32") (pintype "output"))
    )
    (net (code "102") (name "PGOOD") (class "Default")
      (node (ref "PS2") (pin "17") (pinfunction "PGOOD_17") (pintype "output"))
      (node (ref "RPMU12") (pin "1") (pinfunction "1_1") (pintype "passive"))
    )
    (net (code "103") (name "RF_EMITTER") (class "Default")
      (node (ref "R6") (pin "2") (pinfunction "2_2") (pintype "passive"))
      (node (ref "T8") (pin "G") (pinfunction "G_G") (pintype "passive"))
      (node (ref "U1") (pin "28") (pinfunction "IO17_28") (pintype "bidirectional"))
    )
    (net (code "104") (name "RF_RECEIVER") (class "Default")
      (node (ref "Q7") (pin "2") (pinfunction "E_2") (pintype "passive"))
      (node (ref "R20") (pin "2") (pinfunction "2_2") (pintype "passive"))
      (node (ref "U1") (pin "17") (pinfunction "SD2_17") (pintype "bidirectional"))
    )
    (net (code "105") (name "RPWMA") (class "Default")
      (node (ref "IC6") (pin "2") (pinfunction "INA_2") (pintype "bidirectional"))
      (node (ref "R29") (pin "1") (pinfunction "1_1") (pintype "passive"))
      (node (ref "U1") (pin "27") (pinfunction "IO16_27") (pintype "bidirectional"))
    )
    (net (code "106") (name "RPWMB") (class "Default")
      (node (ref "IC6") (pin "4") (pinfunction "INB_4") (pintype "bidirectional"))
      (node (ref "R30") (pin "1") (pinfunction "1_1") (pintype "passive"))
      (node (ref "U1") (pin "29") (pinfunction "IO5_29") (pintype "bidirectional"))
    )
    (net (code "107") (name "RST_N") (class "Default")
      (node (ref "PS2") (pin "39") (pinfunction "RST_N_39") (pintype "input"))
      (node (ref "RPMU9") (pin "1") (pinfunction "1_1") (pintype "passive"))
    )
    (net (code "108") (name "RXD") (class "Default")
      (node (ref "U1") (pin "34") (pinfunction "RXD0_34") (pintype "bidirectional"))
      (node (ref "UART") (pin "3") (pinfunction "3_3") (pintype "passive"))
    )
    (net (code "109") (name "R_EMITTER") (class "Default")
      (node (ref "R9") (pin "2") (pinfunction "2_2") (pintype "passive"))
      (node (ref "T7") (pin "G") (pinfunction "G_G") (pintype "passive"))
      (node (ref "U1") (pin "33") (pinfunction "IO21_33") (pintype "bidirectional"))
    )
    (net (code "110") (name "R_ENC_A") (class "Default")
      (node (ref "J5") (pin "1") (pinfunction "1_1") (pintype "bidirectional"))
      (node (ref "U1") (pin "7") (pinfunction "IO35_7") (pintype "input"))
    )
    (net (code "111") (name "R_ENC_B") (class "Default")
      (node (ref "J5") (pin "2") (pinfunction "2_2") (pintype "bidirectional"))
      (node (ref "U1") (pin "6") (pinfunction "IO34_6") (pintype "input"))
    )
    (net (code "112") (name "R_RECEIVER1") (class "Default")
      (node (ref "Q5") (pin "2") (pinfunction "E_2") (pintype "passive"))
      (node (ref "R18") (pin "2") (pinfunction "2_2") (pintype "passive"))
      (node (ref "U1") (pin "18") (pinfunction "SD3_18") (pintype "bidirectional"))
    )
    (net (code "113") (name "R_RECEIVER2") (class "Default")
      (node (ref "Q6") (pin "2") (pinfunction "E_2") (pintype "passive"))
      (node (ref "R19") (pin "2") (pinfunction "2_2") (pintype "passive"))
      (node (ref "U1") (pin "19") (pinfunction "CMD_19") (pintype "bidirectional"))
    )
    (net (code "114") (name "SCL") (class "Default")
      (node (ref "R2") (pin "1") (pinfunction "1_1") (pintype "passive"))
      (node (ref "U$8") (pin "18") (pinfunction "D0_18") (pintype "bidirectional"))
      (node (ref "U1") (pin "12") (pinfunction "IO27_12") (pintype "bidirectional"))
    )
    (net (code "115") (name "SCLK") (class "Default")
      (node (ref "IC3") (pin "23") (pinfunction "SCL/SCLK_23") (pintype "bidirectional"))
      (node (ref "U1") (pin "10") (pinfunction "IO25_10") (pintype "bidirectional"))
    )
    (net (code "116") (name "SCLPMU") (class "Default")
      (node (ref "PS2") (pin "43") (pinfunction "SCL_43") (pintype "input"))
      (node (ref "RPMU11") (pin "1") (pinfunction "1_1") (pintype "passive"))
    )
    (net (code "117") (name "SDA") (class "Default")
      (node (ref "R3") (pin "1") (pinfunction "1_1") (pintype "passive"))
      (node (ref "U$8") (pin "19") (pinfunction "D1_19") (pintype "bidirectional"))
      (node (ref "U$8") (pin "20") (pinfunction "D2_20") (pintype "bidirectional"))
      (node (ref "U1") (pin "37") (pinfunction "IO23_37") (pintype "bidirectional"))
    )
    (net (code "118") (name "SDAPMU") (class "Default")
      (node (ref "PS2") (pin "42") (pinfunction "SDA_42") (pintype "bidirectional"))
      (node (ref "RPMU10") (pin "1") (pinfunction "1_1") (pintype "passive"))
    )
    (net (code "119") (name "SDI") (class "Default")
      (node (ref "IC3") (pin "24") (pinfunction "SDA/SDI_24") (pintype "bidirectional"))
      (node (ref "U1") (pin "9") (pinfunction "IO33_9") (pintype "bidirectional"))
    )
    (net (code "120") (name "SDO") (class "Default")
      (node (ref "IC3") (pin "9") (pinfunction "SDO/AD0_9") (pintype "bidirectional"))
      (node (ref "U1") (pin "8") (pinfunction "IO32_8") (pintype "bidirectional"))
    )
    (net (code "121") (name "TDI") (class "Default")
      (node (ref "J3") (pin "2") (pinfunction "2_2") (pintype "passive"))
      (node (ref "U1") (pin "14") (pinfunction "IO12_14") (pintype "bidirectional"))
    )
    (net (code "122") (name "TXD") (class "Default")
      (node (ref "U1") (pin "35") (pinfunction "TXD0_35") (pintype "bidirectional"))
      (node (ref "UART") (pin "4") (pinfunction "4_4") (pintype "passive"))
    )
    (net (code "123") (name "VBATT") (class "Default")
      (node (ref "C45") (pin "1") (pinfunction "1_1") (pintype "passive"))
      (node (ref "C6") (pin "1") (pinfunction "1_1") (pintype "passive"))
      (node (ref "C8") (pin "2") (pinfunction "2_2") (pintype "passive"))
      (node (ref "CIN1") (pin "1") (pinfunction "1_1") (pintype "passive"))
      (node (ref "CIN2") (pin "1") (pinfunction "1_1") (pintype "passive"))
      (node (ref "D3") (pin "A") (pinfunction "A_A") (pintype "passive"))
      (node (ref "D5") (pin "A") (pinfunction "A_A") (pintype "passive"))
      (node (ref "IC1") (pin "9") (pinfunction "VBN_9") (pintype "bidirectional"))
      (node (ref "J2") (pin "P$1") (pinfunction "P$1_P$1") (pintype "bidirectional"))
      (node (ref "PLZ6V2B-G3/H") (pin "K") (pinfunction "K_K") (pintype "bidirectional"))
      (node (ref "PS2") (pin "22") (pinfunction "VIN_22") (pintype "power_in"))
      (node (ref "PS2") (pin "30") (pinfunction "PVIN3_30") (pintype "power_in"))
      (node (ref "PS2") (pin "31") (pinfunction "PVIN4_31") (pintype "power_in"))
      (node (ref "PS2") (pin "5") (pinfunction "PVIN1_5") (pintype "power_in"))
      (node (ref "PS2") (pin "6") (pinfunction "PVIN2_6") (pintype "power_in"))
      (node (ref "U$9") (pin "P$1") (pinfunction "1_P$1") (pintype "bidirectional"))
    )
    (net (code "124") (name "VBOOST") (class "Default")
      (node (ref "C33") (pin "1") (pinfunction "1_1") (pintype "passive"))
      (node (ref "C34") (pin "1") (pinfunction "1_1") (pintype "passive"))
      (node (ref "C35") (pin "1") (pinfunction "1_1") (pintype "passive"))
      (node (ref "C36") (pin "1") (pinfunction "1_1") (pintype "passive"))
      (node (ref "C37") (pin "1") (pinfunction "1_1") (pintype "passive"))
      (node (ref "C38") (pin "1") (pinfunction "1_1") (pintype "passive"))
      (node (ref "C46") (pin "1") (pinfunction "1_1") (pintype "passive"))
      (node (ref "C49") (pin "1") (pinfunction "1_1") (pintype "passive"))
      (node (ref "C50") (pin "1") (pinfunction "1_1") (pintype "passive"))
      (node (ref "IC1") (pin "14") (pinfunction "VOUT_1_14") (pintype "bidirectional"))
      (node (ref "IC1") (pin "15") (pinfunction "VOUT_2_15") (pintype "bidirectional"))
      (node (ref "IC1") (pin "16") (pinfunction "VOUT_3_16") (pintype "bidirectional"))
      (node (ref "IC6") (pin "6") (pinfunction "VDD_6") (pintype "bidirectional"))
      (node (ref "IC8") (pin "6") (pinfunction "VDD_6") (pintype "bidirectional"))
      (node (ref "IC9") (pin "5") (pinfunction "OUTB_5") (pintype "bidirectional"))
      (node (ref "Q10") (pin "7") (pinfunction "P1S/P2S_7") (pintype "bidirectional"))
      (node (ref "Q11") (pin "7") (pinfunction "P1S/P2S_7") (pintype "bidirectional"))
      (node (ref "R25") (pin "2") (pinfunction "2_2") (pintype "passive"))
    )
    (net (code "125") (name "VDDD") (class "Default")
      (node (ref "CVDD1") (pin "1") (pinfunction "1_1") (pintype "passive"))
      (node (ref "PS2") (pin "13") (pinfunction "ENSW2_13") (pintype "input"))
      (node (ref "PS2") (pin "20") (pinfunction "VDDD_20") (pintype "output"))
      (node (ref "PS2") (pin "27") (pinfunction "ENSW3_27") (pintype "input"))
      (node (ref "PS2") (pin "34") (pinfunction "ENSW4_34") (pintype "input"))
      (node (ref "PS2") (pin "48") (pinfunction "ENS1_48") (pintype "input"))
      (node (ref "RPMU10") (pin "2") (pinfunction "2_2") (pintype "passive"))
      (node (ref "RPMU11") (pin "2") (pinfunction "2_2") (pintype "passive"))
      (node (ref "RPMU12") (pin "2") (pinfunction "2_2") (pintype "passive"))
      (node (ref "RPMU8") (pin "2") (pinfunction "2_2") (pintype "passive"))
      (node (ref "RPMU9") (pin "2") (pinfunction "2_2") (pintype "passive"))
    )
    (net (code "126") (name "unconnected-(IC1-EN-Pad2)") (class "Default")
      (node (ref "IC1") (pin "2") (pinfunction "EN_2") (pintype "bidirectional"))
    )
    (net (code "127") (name "unconnected-(IC1-MODE-Pad13)") (class "Default")
      (node (ref "IC1") (pin "13") (pinfunction "MODE_13") (pintype "bidirectional"))
    )
    (net (code "128") (name "unconnected-(IC3-AUX-Pad7)") (class "Default")
      (node (ref "IC3") (pin "7") (pinfunction "AUX_7") (pintype "bidirectional"))
    )
    (net (code "129") (name "unconnected-(IC3-AUX_DA-Pad21)") (class "Default")
      (node (ref "IC3") (pin "21") (pinfunction "AUX_DA_21") (pintype "bidirectional"))
    )
    (net (code "130") (name "unconnected-(IC3-NC_1-Pad1)") (class "Default")
      (node (ref "IC3") (pin "1") (pinfunction "NC_1_1") (pintype "bidirectional"))
    )
    (net (code "131") (name "unconnected-(IC3-NC_2-Pad2)") (class "Default")
      (node (ref "IC3") (pin "2") (pinfunction "NC_2_2") (pintype "bidirectional"))
    )
    (net (code "132") (name "unconnected-(IC3-NC_3-Pad3)") (class "Default")
      (node (ref "IC3") (pin "3") (pinfunction "NC_3_3") (pintype "bidirectional"))
    )
    (net (code "133") (name "unconnected-(IC3-NC_4-Pad4)") (class "Default")
      (node (ref "IC3") (pin "4") (pinfunction "NC_4_4") (pintype "bidirectional"))
    )
    (net (code "134") (name "unconnected-(IC3-NC_5-Pad5)") (class "Default")
      (node (ref "IC3") (pin "5") (pinfunction "NC_5_5") (pintype "bidirectional"))
    )
    (net (code "135") (name "unconnected-(IC3-NC_6-Pad6)") (class "Default")
      (node (ref "IC3") (pin "6") (pinfunction "NC_6_6") (pintype "bidirectional"))
    )
    (net (code "136") (name "unconnected-(IC3-NC_7-Pad14)") (class "Default")
      (node (ref "IC3") (pin "14") (pinfunction "NC_7_14") (pintype "bidirectional"))
    )
    (net (code "137") (name "unconnected-(IC3-NC_8-Pad15)") (class "Default")
      (node (ref "IC3") (pin "15") (pinfunction "NC_8_15") (pintype "bidirectional"))
    )
    (net (code "138") (name "unconnected-(IC3-NC_9-Pad16)") (class "Default")
      (node (ref "IC3") (pin "16") (pinfunction "NC_9_16") (pintype "bidirectional"))
    )
    (net (code "139") (name "unconnected-(IC3-NC_10-Pad17)") (class "Default")
      (node (ref "IC3") (pin "17") (pinfunction "NC_10_17") (pintype "bidirectional"))
    )
    (net (code "140") (name "unconnected-(IC3-RESV_1-Pad19)") (class "Default")
      (node (ref "IC3") (pin "19") (pinfunction "RESV_1_19") (pintype "bidirectional"))
    )
    (net (code "141") (name "unconnected-(IC3-RESV_2-Pad20)") (class "Default")
      (node (ref "IC3") (pin "20") (pinfunction "RESV_2_20") (pintype "bidirectional"))
    )
    (net (code "142") (name "unconnected-(IC6-ENA-Pad1)") (class "Default")
      (node (ref "IC6") (pin "1") (pinfunction "ENA_1") (pintype "bidirectional"))
    )
    (net (code "143") (name "unconnected-(IC6-ENB-Pad8)") (class "Default")
      (node (ref "IC6") (pin "8") (pinfunction "ENB_8") (pintype "bidirectional"))
    )
    (net (code "144") (name "unconnected-(IC8-ENA-Pad1)") (class "Default")
      (node (ref "IC8") (pin "1") (pinfunction "ENA_1") (pintype "bidirectional"))
    )
    (net (code "145") (name "unconnected-(IC8-ENB-Pad8)") (class "Default")
      (node (ref "IC8") (pin "8") (pinfunction "ENB_8") (pintype "bidirectional"))
    )
    (net (code "146") (name "unconnected-(IC9-ENA-Pad1)") (class "Default")
      (node (ref "IC9") (pin "1") (pinfunction "ENA_1") (pintype "bidirectional"))
    )
    (net (code "147") (name "unconnected-(IC9-ENB-Pad8)") (class "Default")
      (node (ref "IC9") (pin "8") (pinfunction "ENB_8") (pintype "bidirectional"))
    )
    (net (code "148") (name "unconnected-(IC9-INA-Pad2)") (class "Default")
      (node (ref "IC9") (pin "2") (pinfunction "INA_2") (pintype "bidirectional"))
    )
    (net (code "149") (name "unconnected-(IC9-OUTA-Pad7)") (class "Default")
      (node (ref "IC9") (pin "7") (pinfunction "OUTA_7") (pintype "bidirectional"))
    )
    (net (code "150") (name "unconnected-(PS2-CE-Pad23)") (class "Default")
      (node (ref "PS2") (pin "23") (pinfunction "CE_23") (pintype "input"))
    )
    (net (code "151") (name "unconnected-(PS2-CLK_OUT-Pad44)") (class "Default")
      (node (ref "PS2") (pin "44") (pinfunction "CLK_OUT_44") (pintype "output"))
    )
    (net (code "152") (name "unconnected-(U$8-D{slash}C#-Pad15)") (class "Default")
      (node (ref "U$8") (pin "15") (pinfunction "D/C#_15") (pintype "bidirectional"))
    )
    (net (code "153") (name "unconnected-(U$8-NC_2-Pad7)") (class "Default")
      (node (ref "U$8") (pin "7") (pinfunction "NC_2_7") (pintype "bidirectional"))
    )
    (net (code "154") (name "unconnected-(U1-NC-Pad32)") (class "Default")
      (node (ref "U1") (pin "32") (pinfunction "NC_32") (pintype "bidirectional"))
    )
  )
)
